# mixer.net
KiCad netlist of a schematic drawn in EAGLE
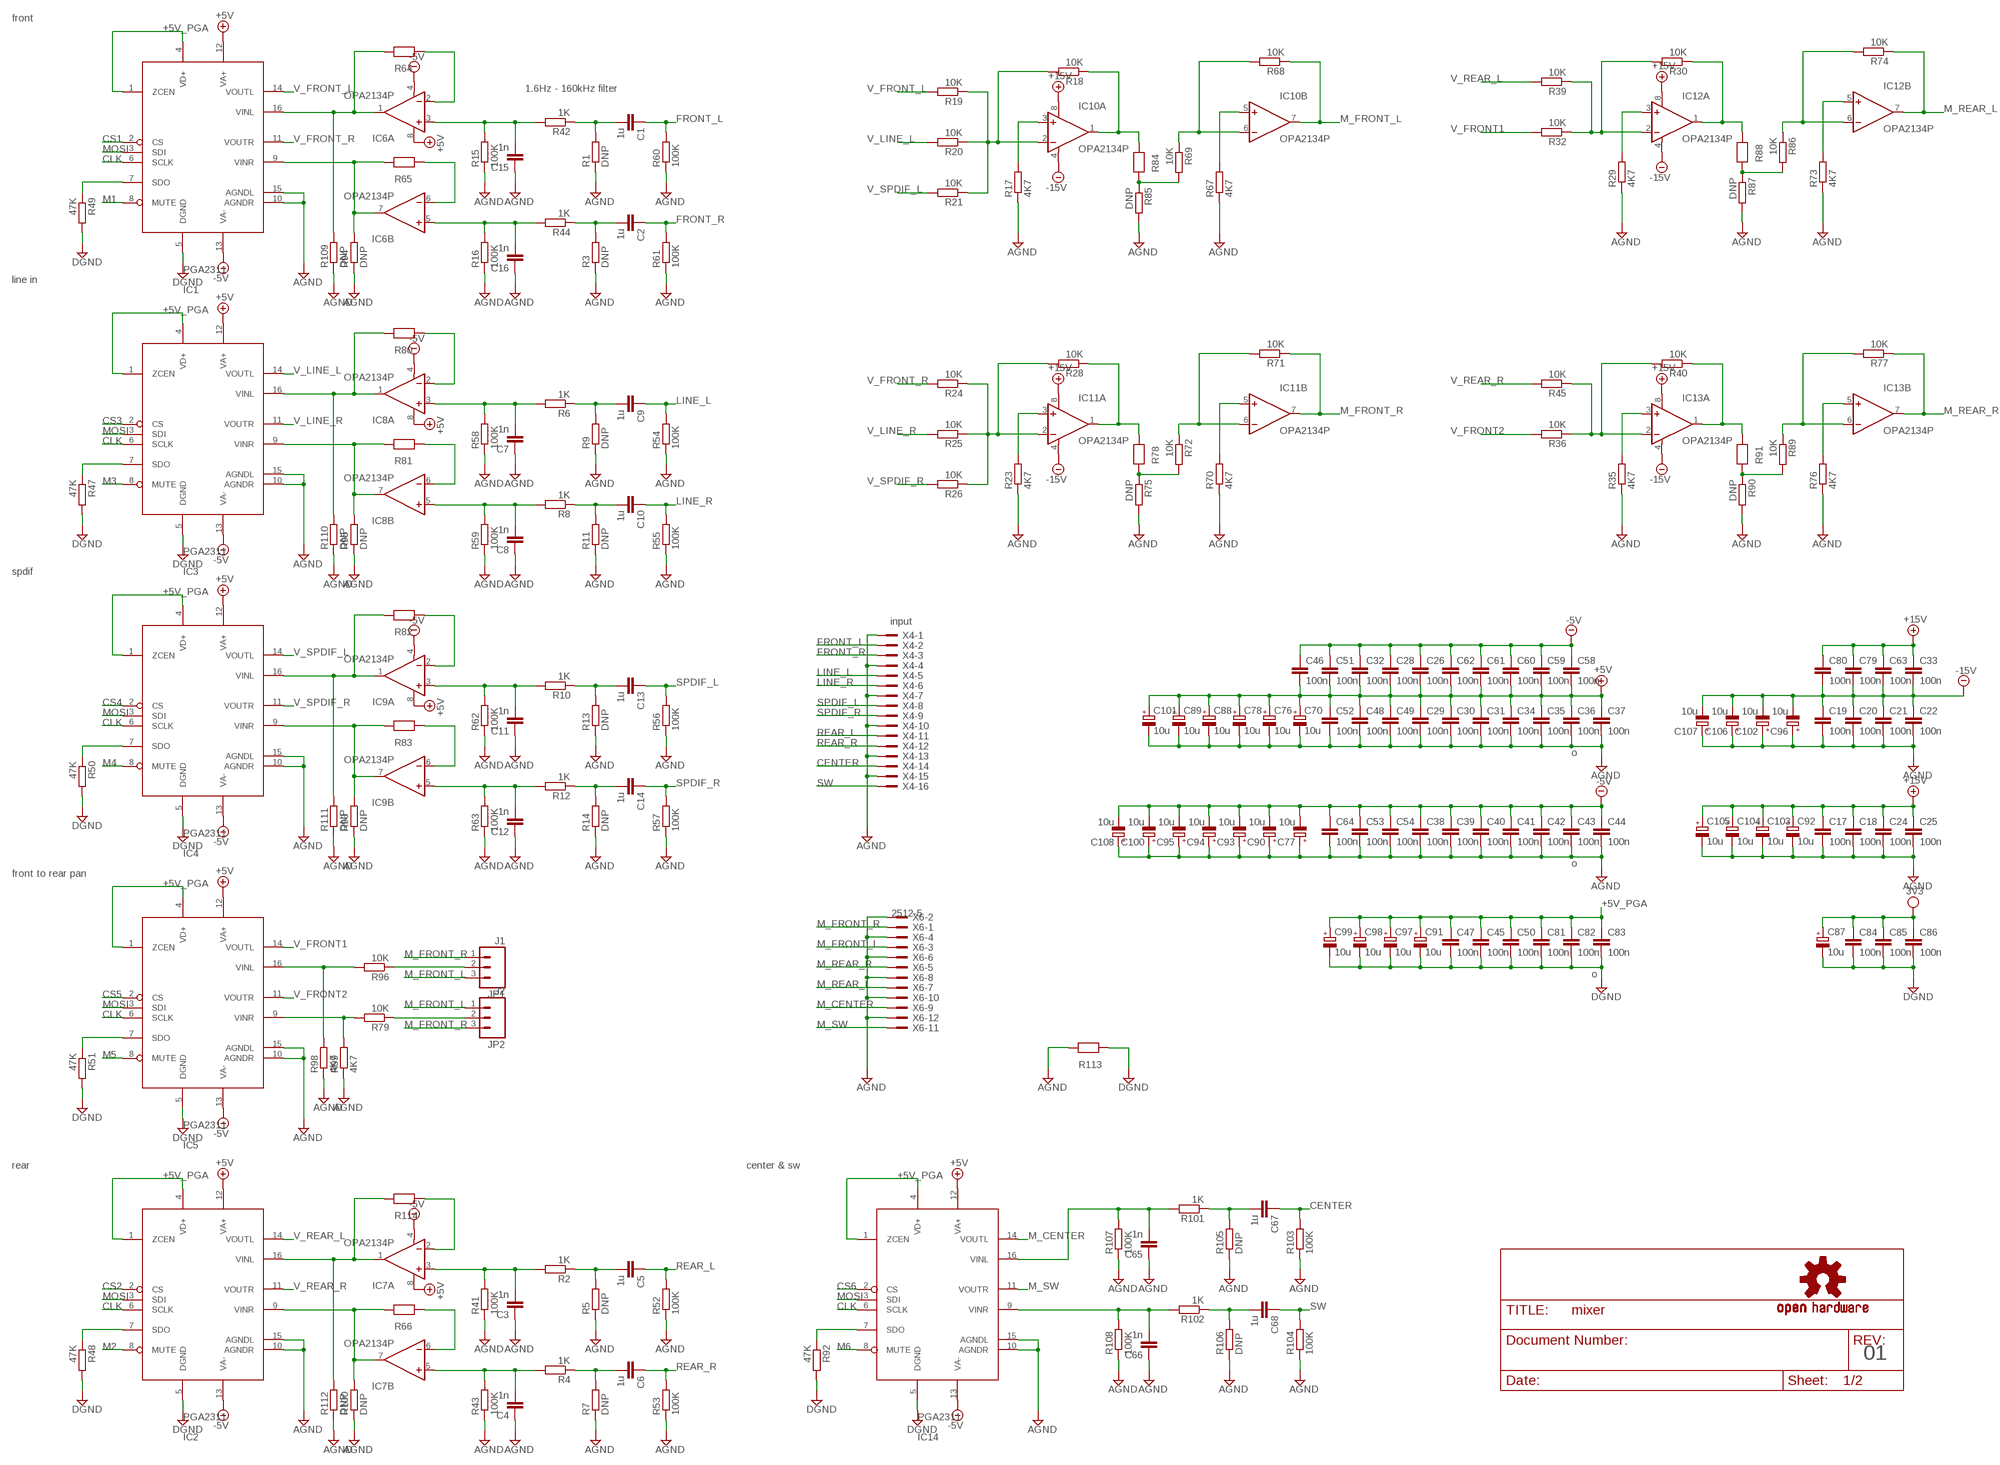
[diagram p0: schematic, sheet 1]
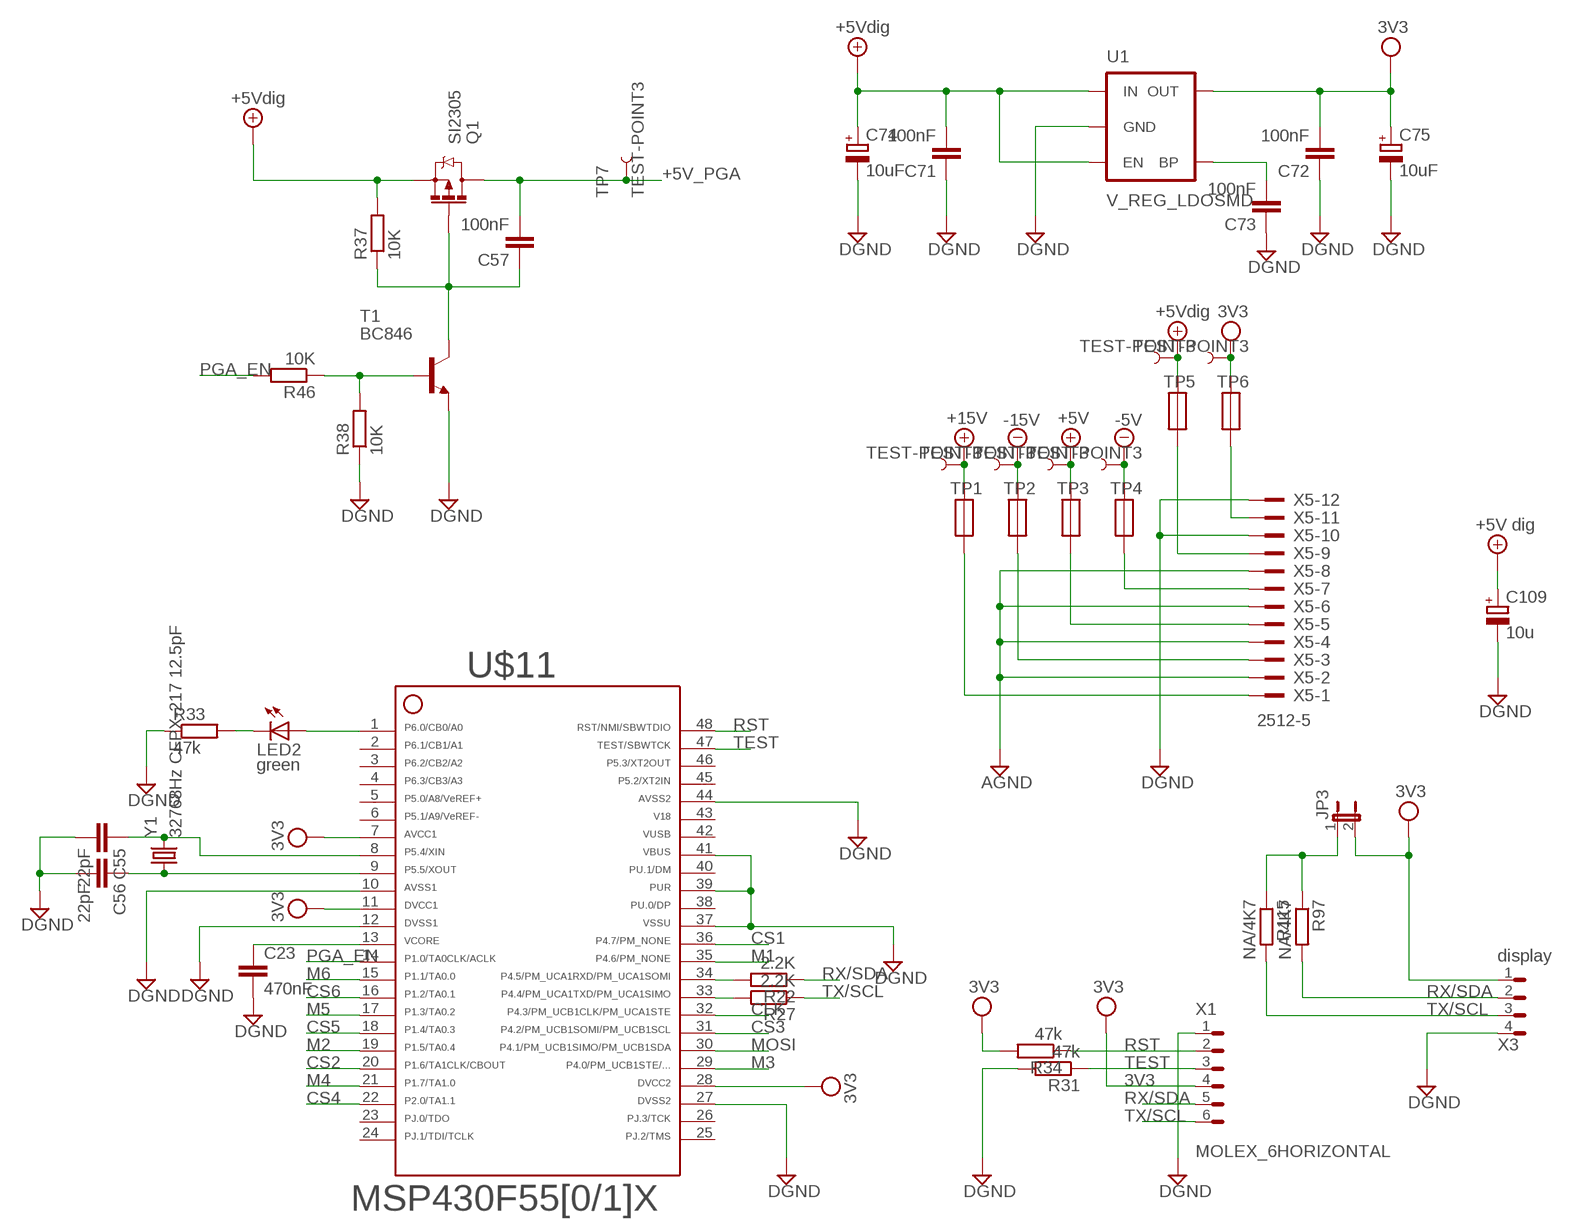
[diagram p1: schematic, sheet 2]

(export (version "E")
  (design (tool "Eeschema 10.0.6"))
  (components
    (comp (ref "C23")
      (value "470nF")
      (footprint "eagle-import:C0805")
      (libsource (lib "eagle-import") (part "C-EUC0805"))
    )
    (comp (ref "C55")
      (value "22pF")
      (footprint "eagle-import:C0805")
      (libsource (lib "eagle-import") (part "C-EUC0805"))
    )
    (comp (ref "C56")
      (value "22pF")
      (footprint "eagle-import:C0805")
      (libsource (lib "eagle-import") (part "C-EUC0805"))
    )
    (comp (ref "C57")
      (value "100nF")
      (footprint "eagle-import:C0805")
      (libsource (lib "eagle-import") (part "C-EUC0805"))
    )
    (comp (ref "C71")
      (value "100nF")
      (footprint "eagle-import:C0805")
      (libsource (lib "eagle-import") (part "C-EUC0805"))
    )
    (comp (ref "C72")
      (value "100nF")
      (footprint "eagle-import:C0805")
      (libsource (lib "eagle-import") (part "C-EUC0805"))
    )
    (comp (ref "C73")
      (value "100nF")
      (footprint "eagle-import:C0805")
      (libsource (lib "eagle-import") (part "C-EUC0805"))
    )
    (comp (ref "C74")
      (value "10uF")
      (footprint "eagle-import:153CLV-0405")
      (libsource (lib "eagle-import") (part "resistor_CPOL-EU153CLV-0405"))
    )
    (comp (ref "C75")
      (value "10uF")
      (footprint "eagle-import:153CLV-0405")
      (libsource (lib "eagle-import") (part "resistor_CPOL-EU153CLV-0405"))
    )
    (comp (ref "C109")
      (value "10u")
      (footprint "eagle-import:153CLV-0405")
      (libsource (lib "eagle-import") (part "CPOL-EU153CLV-0405"))
    )
    (comp (ref "JP3")
      (value "JUMPER-2SMD-NO")
      (footprint "eagle-import:SJ_2S-NO")
      (libsource (lib "eagle-import") (part "JUMPER-2SMD-NO"))
    )
    (comp (ref "LED2")
      (value "green")
      (footprint "eagle-import:CHIPLED_0805")
      (libsource (lib "eagle-import") (part "LEDCHIPLED_0805"))
    )
    (comp (ref "Q1")
      (value "SI2305")
      (footprint "eagle-import:SOT23-3_POWER")
      (libsource (lib "eagle-import") (part "MOSFET-PCHANNEL_SOT23-3_POWER"))
    )
    (comp (ref "R22")
      (value "2.2K")
      (footprint "eagle-import:R0805W")
      (libsource (lib "eagle-import") (part "R-EU_R0805W"))
    )
    (comp (ref "R27")
      (value "2.2K")
      (footprint "eagle-import:R0805W")
      (libsource (lib "eagle-import") (part "R-EU_R0805W"))
    )
    (comp (ref "R31")
      (value "47k")
      (footprint "eagle-import:R0805W")
      (libsource (lib "eagle-import") (part "R-EU_R0805W"))
    )
    (comp (ref "R33")
      (value "47k")
      (footprint "eagle-import:R0805W")
      (libsource (lib "eagle-import") (part "R-EU_R0805W"))
    )
    (comp (ref "R34")
      (value "47k")
      (footprint "eagle-import:R0805W")
      (libsource (lib "eagle-import") (part "R-EU_R0805W"))
    )
    (comp (ref "R37")
      (value "10K")
      (footprint "eagle-import:R0805W")
      (libsource (lib "eagle-import") (part "R-EU_R0805W"))
    )
    (comp (ref "R38")
      (value "10K")
      (footprint "eagle-import:R0805W")
      (libsource (lib "eagle-import") (part "R-EU_R0805W"))
    )
    (comp (ref "R46")
      (value "10K")
      (footprint "eagle-import:R0805W")
      (libsource (lib "eagle-import") (part "R-EU_R0805W"))
    )
    (comp (ref "R97")
      (value "NA/4K7")
      (footprint "eagle-import:R0805W")
      (libsource (lib "eagle-import") (part "R-EU_R0805W"))
    )
    (comp (ref "R115")
      (value "NA/4K7")
      (footprint "eagle-import:R0805W")
      (libsource (lib "eagle-import") (part "R-EU_R0805W"))
    )
    (comp (ref "T1")
      (value "BC846")
      (footprint "eagle-import:SOT23")
      (libsource (lib "eagle-import") (part "BC846"))
    )
    (comp (ref "TP1")
      (value "TEST-POINT3")
      (footprint "eagle-import:PAD.03X.03")
      (libsource (lib "eagle-import") (part "TEST-POINT3"))
    )
    (comp (ref "TP2")
      (value "TEST-POINT3")
      (footprint "eagle-import:PAD.03X.03")
      (libsource (lib "eagle-import") (part "TEST-POINT3"))
    )
    (comp (ref "TP3")
      (value "TEST-POINT3")
      (footprint "eagle-import:PAD.03X.03")
      (libsource (lib "eagle-import") (part "TEST-POINT3"))
    )
    (comp (ref "TP4")
      (value "TEST-POINT3")
      (footprint "eagle-import:PAD.03X.03")
      (libsource (lib "eagle-import") (part "TEST-POINT3"))
    )
    (comp (ref "TP5")
      (value "TEST-POINT3")
      (footprint "eagle-import:PAD.03X.03")
      (libsource (lib "eagle-import") (part "TEST-POINT3"))
    )
    (comp (ref "TP6")
      (value "TEST-POINT3")
      (footprint "eagle-import:PAD.03X.03")
      (libsource (lib "eagle-import") (part "TEST-POINT3"))
    )
    (comp (ref "TP7")
      (value "TEST-POINT3")
      (footprint "eagle-import:PAD.03X.03")
      (libsource (lib "eagle-import") (part "TEST-POINT3"))
    )
    (comp (ref "U$2")
      (value "RESETTABLE")
      (footprint "eagle-import:1210")
      (libsource (lib "eagle-import") (part "RESETTABLE"))
    )
    (comp (ref "U$5")
      (value "RESETTABLE")
      (footprint "eagle-import:1210")
      (libsource (lib "eagle-import") (part "RESETTABLE"))
    )
    (comp (ref "U$6")
      (value "RESETTABLE")
      (footprint "eagle-import:1210")
      (libsource (lib "eagle-import") (part "RESETTABLE"))
    )
    (comp (ref "U$9")
      (value "RESETTABLE")
      (footprint "eagle-import:1210")
      (libsource (lib "eagle-import") (part "RESETTABLE"))
    )
    (comp (ref "U$11")
      (value "F55[0/1]X---PT48")
      (footprint "eagle-import:PT48")
      (libsource (lib "eagle-import") (part "F55[0/1]X---PT48"))
    )
    (comp (ref "U$12")
      (value "RESETTABLE")
      (footprint "eagle-import:1210")
      (libsource (lib "eagle-import") (part "RESETTABLE"))
    )
    (comp (ref "U$13")
      (value "RESETTABLE")
      (footprint "eagle-import:1210")
      (libsource (lib "eagle-import") (part "RESETTABLE"))
    )
    (comp (ref "U1")
      (value "V_REG_LDOSMD")
      (footprint "eagle-import:SOT23-5")
      (libsource (lib "eagle-import") (part "V_REG_LDOSMD"))
    )
    (comp (ref "X1")
      (value "MOLEX_6HORIZONTAL")
      (footprint "eagle-import:0530480610")
      (libsource (lib "eagle-import") (part "MOLEX_6HORIZONTAL"))
    )
    (comp (ref "X3")
      (value "display")
      (footprint "eagle-import:0530480401")
      (libsource (lib "eagle-import") (part "MOLEX_4HORIZONTAL"))
    )
    (comp (ref "X5")
      (value "2512-5")
      (footprint "eagle-import:PAK100_2500-5-12")
      (fields (field (name "MPN") "N2514-5002RB"))
      (libsource (lib "eagle-import") (part "2512-5"))
    )
    (comp (ref "Y1")
      (value "32768Hz CFPX-217 12.5pF")
      (footprint "eagle-import:CRYSTAL-SMD-3.2X1.5")
      (libsource (lib "eagle-import") (part "CRYSTAL3.2X1.5"))
    )
    (comp (ref "C1")
      (value "1u")
      (footprint "eagle-import:C0805")
      (libsource (lib "eagle-import") (part "C-EUC0805"))
    )
    (comp (ref "C2")
      (value "1u")
      (footprint "eagle-import:C0805")
      (libsource (lib "eagle-import") (part "C-EUC0805"))
    )
    (comp (ref "C3")
      (value "1n")
      (footprint "eagle-import:C0805")
      (libsource (lib "eagle-import") (part "C-EUC0805"))
    )
    (comp (ref "C4")
      (value "1n")
      (footprint "eagle-import:C0805")
      (libsource (lib "eagle-import") (part "C-EUC0805"))
    )
    (comp (ref "C5")
      (value "1u")
      (footprint "eagle-import:C0805")
      (libsource (lib "eagle-import") (part "C-EUC0805"))
    )
    (comp (ref "C6")
      (value "1u")
      (footprint "eagle-import:C0805")
      (libsource (lib "eagle-import") (part "C-EUC0805"))
    )
    (comp (ref "C7")
      (value "1n")
      (footprint "eagle-import:C0805")
      (libsource (lib "eagle-import") (part "C-EUC0805"))
    )
    (comp (ref "C8")
      (value "1n")
      (footprint "eagle-import:C0805")
      (libsource (lib "eagle-import") (part "C-EUC0805"))
    )
    (comp (ref "C9")
      (value "1u")
      (footprint "eagle-import:C0805")
      (libsource (lib "eagle-import") (part "C-EUC0805"))
    )
    (comp (ref "C10")
      (value "1u")
      (footprint "eagle-import:C0805")
      (libsource (lib "eagle-import") (part "C-EUC0805"))
    )
    (comp (ref "C11")
      (value "1n")
      (footprint "eagle-import:C0805")
      (libsource (lib "eagle-import") (part "C-EUC0805"))
    )
    (comp (ref "C12")
      (value "1n")
      (footprint "eagle-import:C0805")
      (libsource (lib "eagle-import") (part "C-EUC0805"))
    )
    (comp (ref "C13")
      (value "1u")
      (footprint "eagle-import:C0805")
      (libsource (lib "eagle-import") (part "C-EUC0805"))
    )
    (comp (ref "C14")
      (value "1u")
      (footprint "eagle-import:C0805")
      (libsource (lib "eagle-import") (part "C-EUC0805"))
    )
    (comp (ref "C15")
      (value "1n")
      (footprint "eagle-import:C0805")
      (libsource (lib "eagle-import") (part "C-EUC0805"))
    )
    (comp (ref "C16")
      (value "1n")
      (footprint "eagle-import:C0805")
      (libsource (lib "eagle-import") (part "C-EUC0805"))
    )
    (comp (ref "C17")
      (value "100n")
      (footprint "eagle-import:C0805")
      (libsource (lib "eagle-import") (part "C-EUC0805"))
    )
    (comp (ref "C18")
      (value "100n")
      (footprint "eagle-import:C0805")
      (libsource (lib "eagle-import") (part "C-EUC0805"))
    )
    (comp (ref "C19")
      (value "100n")
      (footprint "eagle-import:C0805")
      (libsource (lib "eagle-import") (part "C-EUC0805"))
    )
    (comp (ref "C20")
      (value "100n")
      (footprint "eagle-import:C0805")
      (libsource (lib "eagle-import") (part "C-EUC0805"))
    )
    (comp (ref "C21")
      (value "100n")
      (footprint "eagle-import:C0805")
      (libsource (lib "eagle-import") (part "C-EUC0805"))
    )
    (comp (ref "C22")
      (value "100n")
      (footprint "eagle-import:C0805")
      (libsource (lib "eagle-import") (part "C-EUC0805"))
    )
    (comp (ref "C24")
      (value "100n")
      (footprint "eagle-import:C0805")
      (libsource (lib "eagle-import") (part "C-EUC0805"))
    )
    (comp (ref "C25")
      (value "100n")
      (footprint "eagle-import:C0805")
      (libsource (lib "eagle-import") (part "C-EUC0805"))
    )
    (comp (ref "C26")
      (value "100n")
      (footprint "eagle-import:C0805")
      (libsource (lib "eagle-import") (part "C-EUC0805"))
    )
    (comp (ref "C28")
      (value "100n")
      (footprint "eagle-import:C0805")
      (libsource (lib "eagle-import") (part "C-EUC0805"))
    )
    (comp (ref "C29")
      (value "100n")
      (footprint "eagle-import:C0805")
      (libsource (lib "eagle-import") (part "C-EUC0805"))
    )
    (comp (ref "C30")
      (value "100n")
      (footprint "eagle-import:C0805")
      (libsource (lib "eagle-import") (part "C-EUC0805"))
    )
    (comp (ref "C31")
      (value "100n")
      (footprint "eagle-import:C0805")
      (libsource (lib "eagle-import") (part "C-EUC0805"))
    )
    (comp (ref "C32")
      (value "100n")
      (footprint "eagle-import:C0805")
      (libsource (lib "eagle-import") (part "C-EUC0805"))
    )
    (comp (ref "C33")
      (value "100n")
      (footprint "eagle-import:C0805")
      (libsource (lib "eagle-import") (part "C-EUC0805"))
    )
    (comp (ref "C34")
      (value "100n")
      (footprint "eagle-import:C0805")
      (libsource (lib "eagle-import") (part "C-EUC0805"))
    )
    (comp (ref "C35")
      (value "100n")
      (footprint "eagle-import:C0805")
      (libsource (lib "eagle-import") (part "C-EUC0805"))
    )
    (comp (ref "C36")
      (value "100n")
      (footprint "eagle-import:C0805")
      (libsource (lib "eagle-import") (part "C-EUC0805"))
    )
    (comp (ref "C37")
      (value "100n")
      (footprint "eagle-import:C0805")
      (libsource (lib "eagle-import") (part "C-EUC0805"))
    )
    (comp (ref "C38")
      (value "100n")
      (footprint "eagle-import:C0805")
      (libsource (lib "eagle-import") (part "C-EUC0805"))
    )
    (comp (ref "C39")
      (value "100n")
      (footprint "eagle-import:C0805")
      (libsource (lib "eagle-import") (part "C-EUC0805"))
    )
    (comp (ref "C40")
      (value "100n")
      (footprint "eagle-import:C0805")
      (libsource (lib "eagle-import") (part "C-EUC0805"))
    )
    (comp (ref "C41")
      (value "100n")
      (footprint "eagle-import:C0805")
      (libsource (lib "eagle-import") (part "C-EUC0805"))
    )
    (comp (ref "C42")
      (value "100n")
      (footprint "eagle-import:C0805")
      (libsource (lib "eagle-import") (part "C-EUC0805"))
    )
    (comp (ref "C43")
      (value "100n")
      (footprint "eagle-import:C0805")
      (libsource (lib "eagle-import") (part "C-EUC0805"))
    )
    (comp (ref "C44")
      (value "100n")
      (footprint "eagle-import:C0805")
      (libsource (lib "eagle-import") (part "C-EUC0805"))
    )
    (comp (ref "C45")
      (value "100n")
      (footprint "eagle-import:C0805")
      (libsource (lib "eagle-import") (part "C-EUC0805"))
    )
    (comp (ref "C46")
      (value "100n")
      (footprint "eagle-import:C0805")
      (libsource (lib "eagle-import") (part "C-EUC0805"))
    )
    (comp (ref "C47")
      (value "100n")
      (footprint "eagle-import:C0805")
      (libsource (lib "eagle-import") (part "C-EUC0805"))
    )
    (comp (ref "C48")
      (value "100n")
      (footprint "eagle-import:C0805")
      (libsource (lib "eagle-import") (part "C-EUC0805"))
    )
    (comp (ref "C49")
      (value "100n")
      (footprint "eagle-import:C0805")
      (libsource (lib "eagle-import") (part "C-EUC0805"))
    )
    (comp (ref "C50")
      (value "100n")
      (footprint "eagle-import:C0805")
      (libsource (lib "eagle-import") (part "C-EUC0805"))
    )
    (comp (ref "C51")
      (value "100n")
      (footprint "eagle-import:C0805")
      (libsource (lib "eagle-import") (part "C-EUC0805"))
    )
    (comp (ref "C52")
      (value "100n")
      (footprint "eagle-import:C0805")
      (libsource (lib "eagle-import") (part "C-EUC0805"))
    )
    (comp (ref "C53")
      (value "100n")
      (footprint "eagle-import:C0805")
      (libsource (lib "eagle-import") (part "C-EUC0805"))
    )
    (comp (ref "C54")
      (value "100n")
      (footprint "eagle-import:C0805")
      (libsource (lib "eagle-import") (part "C-EUC0805"))
    )
    (comp (ref "C58")
      (value "100n")
      (footprint "eagle-import:C0805")
      (libsource (lib "eagle-import") (part "C-EUC0805"))
    )
    (comp (ref "C59")
      (value "100n")
      (footprint "eagle-import:C0805")
      (libsource (lib "eagle-import") (part "C-EUC0805"))
    )
    (comp (ref "C60")
      (value "100n")
      (footprint "eagle-import:C0805")
      (libsource (lib "eagle-import") (part "C-EUC0805"))
    )
    (comp (ref "C61")
      (value "100n")
      (footprint "eagle-import:C0805")
      (libsource (lib "eagle-import") (part "C-EUC0805"))
    )
    (comp (ref "C62")
      (value "100n")
      (footprint "eagle-import:C0805")
      (libsource (lib "eagle-import") (part "C-EUC0805"))
    )
    (comp (ref "C63")
      (value "100n")
      (footprint "eagle-import:C0805")
      (libsource (lib "eagle-import") (part "C-EUC0805"))
    )
    (comp (ref "C64")
      (value "100n")
      (footprint "eagle-import:C0805")
      (libsource (lib "eagle-import") (part "C-EUC0805"))
    )
    (comp (ref "C65")
      (value "1n")
      (footprint "eagle-import:C0805")
      (libsource (lib "eagle-import") (part "C-EUC0805"))
    )
    (comp (ref "C66")
      (value "1n")
      (footprint "eagle-import:C0805")
      (libsource (lib "eagle-import") (part "C-EUC0805"))
    )
    (comp (ref "C67")
      (value "1u")
      (footprint "eagle-import:C0805")
      (libsource (lib "eagle-import") (part "C-EUC0805"))
    )
    (comp (ref "C68")
      (value "1u")
      (footprint "eagle-import:C0805")
      (libsource (lib "eagle-import") (part "C-EUC0805"))
    )
    (comp (ref "C70")
      (value "10u")
      (footprint "eagle-import:153CLV-0405")
      (libsource (lib "eagle-import") (part "CPOL-EU153CLV-0405"))
    )
    (comp (ref "C76")
      (value "10u")
      (footprint "eagle-import:153CLV-0405")
      (libsource (lib "eagle-import") (part "CPOL-EU153CLV-0405"))
    )
    (comp (ref "C77")
      (value "10u")
      (footprint "eagle-import:153CLV-0405")
      (libsource (lib "eagle-import") (part "CPOL-EU153CLV-0405"))
    )
    (comp (ref "C78")
      (value "10u")
      (footprint "eagle-import:153CLV-0405")
      (libsource (lib "eagle-import") (part "CPOL-EU153CLV-0405"))
    )
    (comp (ref "C79")
      (value "100n")
      (footprint "eagle-import:C0805")
      (libsource (lib "eagle-import") (part "C-EUC0805"))
    )
    (comp (ref "C80")
      (value "100n")
      (footprint "eagle-import:C0805")
      (libsource (lib "eagle-import") (part "C-EUC0805"))
    )
    (comp (ref "C81")
      (value "100n")
      (footprint "eagle-import:C0805")
      (libsource (lib "eagle-import") (part "C-EUC0805"))
    )
    (comp (ref "C82")
      (value "100n")
      (footprint "eagle-import:C0805")
      (libsource (lib "eagle-import") (part "C-EUC0805"))
    )
    (comp (ref "C83")
      (value "100n")
      (footprint "eagle-import:C0805")
      (libsource (lib "eagle-import") (part "C-EUC0805"))
    )
    (comp (ref "C84")
      (value "100n")
      (footprint "eagle-import:C0805")
      (libsource (lib "eagle-import") (part "C-EUC0805"))
    )
    (comp (ref "C85")
      (value "100n")
      (footprint "eagle-import:C0805")
      (libsource (lib "eagle-import") (part "C-EUC0805"))
    )
    (comp (ref "C86")
      (value "100n")
      (footprint "eagle-import:C0805")
      (libsource (lib "eagle-import") (part "C-EUC0805"))
    )
    (comp (ref "C87")
      (value "10u")
      (footprint "eagle-import:153CLV-0405")
      (libsource (lib "eagle-import") (part "CPOL-EU153CLV-0405"))
    )
    (comp (ref "C88")
      (value "10u")
      (footprint "eagle-import:153CLV-0405")
      (libsource (lib "eagle-import") (part "CPOL-EU153CLV-0405"))
    )
    (comp (ref "C89")
      (value "10u")
      (footprint "eagle-import:153CLV-0405")
      (libsource (lib "eagle-import") (part "CPOL-EU153CLV-0405"))
    )
    (comp (ref "C90")
      (value "10u")
      (footprint "eagle-import:153CLV-0405")
      (libsource (lib "eagle-import") (part "CPOL-EU153CLV-0405"))
    )
    (comp (ref "C91")
      (value "10u")
      (footprint "eagle-import:153CLV-0405")
      (libsource (lib "eagle-import") (part "CPOL-EU153CLV-0405"))
    )
    (comp (ref "C92")
      (value "10u")
      (footprint "eagle-import:153CLV-0405")
      (libsource (lib "eagle-import") (part "CPOL-EU153CLV-0405"))
    )
    (comp (ref "C93")
      (value "10u")
      (footprint "eagle-import:153CLV-0405")
      (libsource (lib "eagle-import") (part "CPOL-EU153CLV-0405"))
    )
    (comp (ref "C94")
      (value "10u")
      (footprint "eagle-import:153CLV-0405")
      (libsource (lib "eagle-import") (part "CPOL-EU153CLV-0405"))
    )
    (comp (ref "C95")
      (value "10u")
      (footprint "eagle-import:153CLV-0405")
      (libsource (lib "eagle-import") (part "CPOL-EU153CLV-0405"))
    )
    (comp (ref "C96")
      (value "10u")
      (footprint "eagle-import:153CLV-0405")
      (libsource (lib "eagle-import") (part "CPOL-EU153CLV-0405"))
    )
    (comp (ref "C97")
      (value "10u")
      (footprint "eagle-import:153CLV-0405")
      (libsource (lib "eagle-import") (part "CPOL-EU153CLV-0405"))
    )
    (comp (ref "C98")
      (value "10u")
      (footprint "eagle-import:153CLV-0405")
      (libsource (lib "eagle-import") (part "CPOL-EU153CLV-0405"))
    )
    (comp (ref "C99")
      (value "10u")
      (footprint "eagle-import:153CLV-0405")
      (libsource (lib "eagle-import") (part "CPOL-EU153CLV-0405"))
    )
    (comp (ref "C100")
      (value "10u")
      (footprint "eagle-import:153CLV-0405")
      (libsource (lib "eagle-import") (part "CPOL-EU153CLV-0405"))
    )
    (comp (ref "C101")
      (value "10u")
      (footprint "eagle-import:153CLV-0405")
      (libsource (lib "eagle-import") (part "CPOL-EU153CLV-0405"))
    )
    (comp (ref "C102")
      (value "10u")
      (footprint "eagle-import:153CLV-0405")
      (libsource (lib "eagle-import") (part "CPOL-EU153CLV-0405"))
    )
    (comp (ref "C103")
      (value "10u")
      (footprint "eagle-import:153CLV-0405")
      (libsource (lib "eagle-import") (part "CPOL-EU153CLV-0405"))
    )
    (comp (ref "C104")
      (value "10u")
      (footprint "eagle-import:153CLV-0405")
      (libsource (lib "eagle-import") (part "CPOL-EU153CLV-0405"))
    )
    (comp (ref "C105")
      (value "10u")
      (footprint "eagle-import:153CLV-0405")
      (libsource (lib "eagle-import") (part "CPOL-EU153CLV-0405"))
    )
    (comp (ref "C106")
      (value "10u")
      (footprint "eagle-import:153CLV-0405")
      (libsource (lib "eagle-import") (part "CPOL-EU153CLV-0405"))
    )
    (comp (ref "C107")
      (value "10u")
      (footprint "eagle-import:153CLV-0405")
      (libsource (lib "eagle-import") (part "CPOL-EU153CLV-0405"))
    )
    (comp (ref "C108")
      (value "10u")
      (footprint "eagle-import:153CLV-0405")
      (libsource (lib "eagle-import") (part "CPOL-EU153CLV-0405"))
    )
    (comp (ref "IC1")
      (value "PGA2311")
      (footprint "eagle-import:SO-16")
      (libsource (lib "eagle-import") (part "PGA2311"))
    )
    (comp (ref "IC2")
      (value "PGA2311")
      (footprint "eagle-import:SO-16")
      (libsource (lib "eagle-import") (part "PGA2311"))
    )
    (comp (ref "IC3")
      (value "PGA2311")
      (footprint "eagle-import:SO-16")
      (libsource (lib "eagle-import") (part "PGA2311"))
    )
    (comp (ref "IC4")
      (value "PGA2311")
      (footprint "eagle-import:SO-16")
      (libsource (lib "eagle-import") (part "PGA2311"))
    )
    (comp (ref "IC5")
      (value "PGA2311")
      (footprint "eagle-import:SO-16")
      (libsource (lib "eagle-import") (part "PGA2311"))
    )
    (comp (ref "IC6")
      (value "OPA2134P")
      (footprint "eagle-import:DIL08")
      (fields (field (name "MF") "TEXAS INSTRUMENTS") (field (name "MPN") "OPA2134PA"))
      (libsource (lib "eagle-import") (part "OPA2134P"))
    )
    (comp (ref "IC7")
      (value "OPA2134P")
      (footprint "eagle-import:DIL08")
      (fields (field (name "MF") "TEXAS INSTRUMENTS") (field (name "MPN") "OPA2134PA"))
      (libsource (lib "eagle-import") (part "OPA2134P"))
    )
    (comp (ref "IC8")
      (value "OPA2134P")
      (footprint "eagle-import:DIL08")
      (fields (field (name "MF") "TEXAS INSTRUMENTS") (field (name "MPN") "OPA2134PA"))
      (libsource (lib "eagle-import") (part "OPA2134P"))
    )
    (comp (ref "IC9")
      (value "OPA2134P")
      (footprint "eagle-import:DIL08")
      (fields (field (name "MF") "TEXAS INSTRUMENTS") (field (name "MPN") "OPA2134PA"))
      (libsource (lib "eagle-import") (part "OPA2134P"))
    )
    (comp (ref "IC10")
      (value "OPA2134P")
      (footprint "eagle-import:DIL08")
      (fields (field (name "MF") "TEXAS INSTRUMENTS") (field (name "MPN") "OPA2134PA"))
      (libsource (lib "eagle-import") (part "OPA2134P"))
    )
    (comp (ref "IC11")
      (value "OPA2134P")
      (footprint "eagle-import:DIL08")
      (fields (field (name "MF") "TEXAS INSTRUMENTS") (field (name "MPN") "OPA2134PA"))
      (libsource (lib "eagle-import") (part "OPA2134P"))
    )
    (comp (ref "IC12")
      (value "OPA2134P")
      (footprint "eagle-import:DIL08")
      (fields (field (name "MF") "TEXAS INSTRUMENTS") (field (name "MPN") "OPA2134PA"))
      (libsource (lib "eagle-import") (part "OPA2134P"))
    )
    (comp (ref "IC13")
      (value "OPA2134P")
      (footprint "eagle-import:DIL08")
      (fields (field (name "MF") "TEXAS INSTRUMENTS") (field (name "MPN") "OPA2134PA"))
      (libsource (lib "eagle-import") (part "OPA2134P"))
    )
    (comp (ref "IC14")
      (value "PGA2311")
      (footprint "eagle-import:SO-16")
      (libsource (lib "eagle-import") (part "PGA2311"))
    )
    (comp (ref "JP1")
      (value "J1")
      (footprint "eagle-import:1X03")
      (libsource (lib "eagle-import") (part "M03PTH"))
    )
    (comp (ref "JP2")
      (value "J2")
      (footprint "eagle-import:1X03")
      (libsource (lib "eagle-import") (part "M03PTH"))
    )
    (comp (ref "R1")
      (value "DNP")
      (footprint "eagle-import:R0805W")
      (libsource (lib "eagle-import") (part "R-EU_R0805W"))
    )
    (comp (ref "R2")
      (value "1K")
      (footprint "eagle-import:R0805W")
      (libsource (lib "eagle-import") (part "R-EU_R0805W"))
    )
    (comp (ref "R3")
      (value "DNP")
      (footprint "eagle-import:R0805W")
      (libsource (lib "eagle-import") (part "R-EU_R0805W"))
    )
    (comp (ref "R4")
      (value "1K")
      (footprint "eagle-import:R0805W")
      (libsource (lib "eagle-import") (part "R-EU_R0805W"))
    )
    (comp (ref "R5")
      (value "DNP")
      (footprint "eagle-import:R0805W")
      (libsource (lib "eagle-import") (part "R-EU_R0805W"))
    )
    (comp (ref "R6")
      (value "1K")
      (footprint "eagle-import:R0805W")
      (libsource (lib "eagle-import") (part "R-EU_R0805W"))
    )
    (comp (ref "R7")
      (value "DNP")
      (footprint "eagle-import:R0805W")
      (libsource (lib "eagle-import") (part "R-EU_R0805W"))
    )
    (comp (ref "R8")
      (value "1K")
      (footprint "eagle-import:R0805W")
      (libsource (lib "eagle-import") (part "R-EU_R0805W"))
    )
    (comp (ref "R9")
      (value "DNP")
      (footprint "eagle-import:R0805W")
      (libsource (lib "eagle-import") (part "R-EU_R0805W"))
    )
    (comp (ref "R10")
      (value "1K")
      (footprint "eagle-import:R0805W")
      (libsource (lib "eagle-import") (part "R-EU_R0805W"))
    )
    (comp (ref "R11")
      (value "DNP")
      (footprint "eagle-import:R0805W")
      (libsource (lib "eagle-import") (part "R-EU_R0805W"))
    )
    (comp (ref "R12")
      (value "1K")
      (footprint "eagle-import:R0805W")
      (libsource (lib "eagle-import") (part "R-EU_R0805W"))
    )
    (comp (ref "R13")
      (value "DNP")
      (footprint "eagle-import:R0805W")
      (libsource (lib "eagle-import") (part "R-EU_R0805W"))
    )
    (comp (ref "R14")
      (value "DNP")
      (footprint "eagle-import:R0805W")
      (libsource (lib "eagle-import") (part "R-EU_R0805W"))
    )
    (comp (ref "R15")
      (value "100K")
      (footprint "eagle-import:R0805W")
      (libsource (lib "eagle-import") (part "R-EU_R0805W"))
    )
    (comp (ref "R16")
      (value "100K")
      (footprint "eagle-import:R0805W")
      (libsource (lib "eagle-import") (part "R-EU_R0805W"))
    )
    (comp (ref "R17")
      (value "4K7")
      (footprint "eagle-import:R0805W")
      (libsource (lib "eagle-import") (part "R-EU_R0805W"))
    )
    (comp (ref "R18")
      (value "10K")
      (footprint "eagle-import:R0805W")
      (libsource (lib "eagle-import") (part "R-EU_R0805W"))
    )
    (comp (ref "R19")
      (value "10K")
      (footprint "eagle-import:R0805W")
      (libsource (lib "eagle-import") (part "R-EU_R0805W"))
    )
    (comp (ref "R20")
      (value "10K")
      (footprint "eagle-import:R0805W")
      (libsource (lib "eagle-import") (part "R-EU_R0805W"))
    )
    (comp (ref "R21")
      (value "10K")
      (footprint "eagle-import:R0805W")
      (libsource (lib "eagle-import") (part "R-EU_R0805W"))
    )
    (comp (ref "R23")
      (value "4K7")
      (footprint "eagle-import:R0805W")
      (libsource (lib "eagle-import") (part "R-EU_R0805W"))
    )
    (comp (ref "R24")
      (value "10K")
      (footprint "eagle-import:R0805W")
      (libsource (lib "eagle-import") (part "R-EU_R0805W"))
    )
    (comp (ref "R25")
      (value "10K")
      (footprint "eagle-import:R0805W")
      (libsource (lib "eagle-import") (part "R-EU_R0805W"))
    )
    (comp (ref "R26")
      (value "10K")
      (footprint "eagle-import:R0805W")
      (libsource (lib "eagle-import") (part "R-EU_R0805W"))
    )
    (comp (ref "R28")
      (value "10K")
      (footprint "eagle-import:R0805W")
      (libsource (lib "eagle-import") (part "R-EU_R0805W"))
    )
    (comp (ref "R29")
      (value "4K7")
      (footprint "eagle-import:R0805W")
      (libsource (lib "eagle-import") (part "R-EU_R0805W"))
    )
    (comp (ref "R30")
      (value "10K")
      (footprint "eagle-import:R0805W")
      (libsource (lib "eagle-import") (part "R-EU_R0805W"))
    )
    (comp (ref "R32")
      (value "10K")
      (footprint "eagle-import:R0805W")
      (libsource (lib "eagle-import") (part "R-EU_R0805W"))
    )
    (comp (ref "R35")
      (value "4K7")
      (footprint "eagle-import:R0805W")
      (libsource (lib "eagle-import") (part "R-EU_R0805W"))
    )
    (comp (ref "R36")
      (value "10K")
      (footprint "eagle-import:R0805W")
      (libsource (lib "eagle-import") (part "R-EU_R0805W"))
    )
    (comp (ref "R39")
      (value "10K")
      (footprint "eagle-import:R0805W")
      (libsource (lib "eagle-import") (part "R-EU_R0805W"))
    )
    (comp (ref "R40")
      (value "10K")
      (footprint "eagle-import:R0805W")
      (libsource (lib "eagle-import") (part "R-EU_R0805W"))
    )
    (comp (ref "R41")
      (value "100K")
      (footprint "eagle-import:R0805W")
      (libsource (lib "eagle-import") (part "R-EU_R0805W"))
    )
    (comp (ref "R42")
      (value "1K")
      (footprint "eagle-import:R0805W")
      (libsource (lib "eagle-import") (part "R-EU_R0805W"))
    )
    (comp (ref "R43")
      (value "100K")
      (footprint "eagle-import:R0805W")
      (libsource (lib "eagle-import") (part "R-EU_R0805W"))
    )
    (comp (ref "R44")
      (value "1K")
      (footprint "eagle-import:R0805W")
      (libsource (lib "eagle-import") (part "R-EU_R0805W"))
    )
    (comp (ref "R45")
      (value "10K")
      (footprint "eagle-import:R0805W")
      (libsource (lib "eagle-import") (part "R-EU_R0805W"))
    )
    (comp (ref "R47")
      (value "47K")
      (footprint "eagle-import:R0805W")
      (libsource (lib "eagle-import") (part "R-EU_R0805W"))
    )
    (comp (ref "R48")
      (value "47K")
      (footprint "eagle-import:R0805W")
      (libsource (lib "eagle-import") (part "R-EU_R0805W"))
    )
    (comp (ref "R49")
      (value "47K")
      (footprint "eagle-import:R0805W")
      (libsource (lib "eagle-import") (part "R-EU_R0805W"))
    )
    (comp (ref "R50")
      (value "47K")
      (footprint "eagle-import:R0805W")
      (libsource (lib "eagle-import") (part "R-EU_R0805W"))
    )
    (comp (ref "R51")
      (value "47K")
      (footprint "eagle-import:R0805W")
      (libsource (lib "eagle-import") (part "R-EU_R0805W"))
    )
    (comp (ref "R52")
      (value "100K")
      (footprint "eagle-import:R0805W")
      (libsource (lib "eagle-import") (part "R-EU_R0805W"))
    )
    (comp (ref "R53")
      (value "100K")
      (footprint "eagle-import:R0805W")
      (libsource (lib "eagle-import") (part "R-EU_R0805W"))
    )
    (comp (ref "R54")
      (value "100K")
      (footprint "eagle-import:R0805W")
      (libsource (lib "eagle-import") (part "R-EU_R0805W"))
    )
    (comp (ref "R55")
      (value "100K")
      (footprint "eagle-import:R0805W")
      (libsource (lib "eagle-import") (part "R-EU_R0805W"))
    )
    (comp (ref "R56")
      (value "100K")
      (footprint "eagle-import:R0805W")
      (libsource (lib "eagle-import") (part "R-EU_R0805W"))
    )
    (comp (ref "R57")
      (value "100K")
      (footprint "eagle-import:R0805W")
      (libsource (lib "eagle-import") (part "R-EU_R0805W"))
    )
    (comp (ref "R58")
      (value "100K")
      (footprint "eagle-import:R0805W")
      (libsource (lib "eagle-import") (part "R-EU_R0805W"))
    )
    (comp (ref "R59")
      (value "100K")
      (footprint "eagle-import:R0805W")
      (libsource (lib "eagle-import") (part "R-EU_R0805W"))
    )
    (comp (ref "R60")
      (value "100K")
      (footprint "eagle-import:R0805W")
      (libsource (lib "eagle-import") (part "R-EU_R0805W"))
    )
    (comp (ref "R61")
      (value "100K")
      (footprint "eagle-import:R0805W")
      (libsource (lib "eagle-import") (part "R-EU_R0805W"))
    )
    (comp (ref "R62")
      (value "100K")
      (footprint "eagle-import:R0805W")
      (libsource (lib "eagle-import") (part "R-EU_R0805W"))
    )
    (comp (ref "R63")
      (value "100K")
      (footprint "eagle-import:R0805W")
      (libsource (lib "eagle-import") (part "R-EU_R0805W"))
    )
    (comp (ref "R64")
      (value "0R_0805")
      (footprint "eagle-import:R0805W")
      (libsource (lib "eagle-import") (part "0R_0805"))
    )
    (comp (ref "R65")
      (value "0R_0805")
      (footprint "eagle-import:R0805W")
      (libsource (lib "eagle-import") (part "0R_0805"))
    )
    (comp (ref "R66")
      (value "0R_0805")
      (footprint "eagle-import:R0805W")
      (libsource (lib "eagle-import") (part "0R_0805"))
    )
    (comp (ref "R67")
      (value "4K7")
      (footprint "eagle-import:R0805W")
      (libsource (lib "eagle-import") (part "R-EU_R0805W"))
    )
    (comp (ref "R68")
      (value "10K")
      (footprint "eagle-import:R0805W")
      (libsource (lib "eagle-import") (part "R-EU_R0805W"))
    )
    (comp (ref "R69")
      (value "10K")
      (footprint "eagle-import:R0805W")
      (libsource (lib "eagle-import") (part "R-EU_R0805W"))
    )
    (comp (ref "R70")
      (value "4K7")
      (footprint "eagle-import:R0805W")
      (libsource (lib "eagle-import") (part "R-EU_R0805W"))
    )
    (comp (ref "R71")
      (value "10K")
      (footprint "eagle-import:R0805W")
      (libsource (lib "eagle-import") (part "R-EU_R0805W"))
    )
    (comp (ref "R72")
      (value "10K")
      (footprint "eagle-import:R0805W")
      (libsource (lib "eagle-import") (part "R-EU_R0805W"))
    )
    (comp (ref "R73")
      (value "4K7")
      (footprint "eagle-import:R0805W")
      (libsource (lib "eagle-import") (part "R-EU_R0805W"))
    )
    (comp (ref "R74")
      (value "10K")
      (footprint "eagle-import:R0805W")
      (libsource (lib "eagle-import") (part "R-EU_R0805W"))
    )
    (comp (ref "R75")
      (value "DNP")
      (footprint "eagle-import:R0805W")
      (libsource (lib "eagle-import") (part "R-EU_R0805W"))
    )
    (comp (ref "R76")
      (value "4K7")
      (footprint "eagle-import:R0805W")
      (libsource (lib "eagle-import") (part "R-EU_R0805W"))
    )
    (comp (ref "R77")
      (value "10K")
      (footprint "eagle-import:R0805W")
      (libsource (lib "eagle-import") (part "R-EU_R0805W"))
    )
    (comp (ref "R78")
      (value "0R_0805")
      (footprint "eagle-import:R0805W")
      (libsource (lib "eagle-import") (part "0R_0805"))
    )
    (comp (ref "R79")
      (value "10K")
      (footprint "eagle-import:R0805W")
      (libsource (lib "eagle-import") (part "R-EU_R0805W"))
    )
    (comp (ref "R80")
      (value "0R_0805")
      (footprint "eagle-import:R0805W")
      (libsource (lib "eagle-import") (part "0R_0805"))
    )
    (comp (ref "R81")
      (value "0R_0805")
      (footprint "eagle-import:R0805W")
      (libsource (lib "eagle-import") (part "0R_0805"))
    )
    (comp (ref "R82")
      (value "0R_0805")
      (footprint "eagle-import:R0805W")
      (libsource (lib "eagle-import") (part "0R_0805"))
    )
    (comp (ref "R83")
      (value "0R_0805")
      (footprint "eagle-import:R0805W")
      (libsource (lib "eagle-import") (part "0R_0805"))
    )
    (comp (ref "R84")
      (value "0R_0805")
      (footprint "eagle-import:R0805W")
      (libsource (lib "eagle-import") (part "0R_0805"))
    )
    (comp (ref "R85")
      (value "DNP")
      (footprint "eagle-import:R0805W")
      (libsource (lib "eagle-import") (part "R-EU_R0805W"))
    )
    (comp (ref "R86")
      (value "10K")
      (footprint "eagle-import:R0805W")
      (libsource (lib "eagle-import") (part "R-EU_R0805W"))
    )
    (comp (ref "R87")
      (value "DNP")
      (footprint "eagle-import:R0805W")
      (libsource (lib "eagle-import") (part "R-EU_R0805W"))
    )
    (comp (ref "R88")
      (value "0R_0805")
      (footprint "eagle-import:R0805W")
      (libsource (lib "eagle-import") (part "0R_0805"))
    )
    (comp (ref "R89")
      (value "10K")
      (footprint "eagle-import:R0805W")
      (libsource (lib "eagle-import") (part "R-EU_R0805W"))
    )
    (comp (ref "R90")
      (value "DNP")
      (footprint "eagle-import:R0805W")
      (libsource (lib "eagle-import") (part "R-EU_R0805W"))
    )
    (comp (ref "R91")
      (value "0R_0805")
      (footprint "eagle-import:R0805W")
      (libsource (lib "eagle-import") (part "0R_0805"))
    )
    (comp (ref "R92")
      (value "47K")
      (footprint "eagle-import:R0805W")
      (libsource (lib "eagle-import") (part "R-EU_R0805W"))
    )
    (comp (ref "R93")
      (value "DNP")
      (footprint "eagle-import:R0805W")
      (libsource (lib "eagle-import") (part "R-EU_R0805W"))
    )
    (comp (ref "R94")
      (value "DNP")
      (footprint "eagle-import:R0805W")
      (libsource (lib "eagle-import") (part "R-EU_R0805W"))
    )
    (comp (ref "R95")
      (value "DNP")
      (footprint "eagle-import:R0805W")
      (libsource (lib "eagle-import") (part "R-EU_R0805W"))
    )
    (comp (ref "R96")
      (value "10K")
      (footprint "eagle-import:R0805W")
      (libsource (lib "eagle-import") (part "R-EU_R0805W"))
    )
    (comp (ref "R98")
      (value "4K7")
      (footprint "eagle-import:R0805W")
      (libsource (lib "eagle-import") (part "R-EU_R0805W"))
    )
    (comp (ref "R99")
      (value "4K7")
      (footprint "eagle-import:R0805W")
      (libsource (lib "eagle-import") (part "R-EU_R0805W"))
    )
    (comp (ref "R100")
      (value "DNP")
      (footprint "eagle-import:R0805W")
      (libsource (lib "eagle-import") (part "R-EU_R0805W"))
    )
    (comp (ref "R101")
      (value "1K")
      (footprint "eagle-import:R0805W")
      (libsource (lib "eagle-import") (part "R-EU_R0805W"))
    )
    (comp (ref "R102")
      (value "1K")
      (footprint "eagle-import:R0805W")
      (libsource (lib "eagle-import") (part "R-EU_R0805W"))
    )
    (comp (ref "R103")
      (value "100K")
      (footprint "eagle-import:R0805W")
      (libsource (lib "eagle-import") (part "R-EU_R0805W"))
    )
    (comp (ref "R104")
      (value "100K")
      (footprint "eagle-import:R0805W")
      (libsource (lib "eagle-import") (part "R-EU_R0805W"))
    )
    (comp (ref "R105")
      (value "DNP")
      (footprint "eagle-import:R0805W")
      (libsource (lib "eagle-import") (part "R-EU_R0805W"))
    )
    (comp (ref "R106")
      (value "DNP")
      (footprint "eagle-import:R0805W")
      (libsource (lib "eagle-import") (part "R-EU_R0805W"))
    )
    (comp (ref "R107")
      (value "100K")
      (footprint "eagle-import:R0805W")
      (libsource (lib "eagle-import") (part "R-EU_R0805W"))
    )
    (comp (ref "R108")
      (value "100K")
      (footprint "eagle-import:R0805W")
      (libsource (lib "eagle-import") (part "R-EU_R0805W"))
    )
    (comp (ref "R109")
      (value "DNP")
      (footprint "eagle-import:R0805W")
      (libsource (lib "eagle-import") (part "R-EU_R0805W"))
    )
    (comp (ref "R110")
      (value "DNP")
      (footprint "eagle-import:R0805W")
      (libsource (lib "eagle-import") (part "R-EU_R0805W"))
    )
    (comp (ref "R111")
      (value "DNP")
      (footprint "eagle-import:R0805W")
      (libsource (lib "eagle-import") (part "R-EU_R0805W"))
    )
    (comp (ref "R112")
      (value "DNP")
      (footprint "eagle-import:R0805W")
      (libsource (lib "eagle-import") (part "R-EU_R0805W"))
    )
    (comp (ref "R113")
      (value "0R_0805")
      (footprint "eagle-import:R0805W")
      (libsource (lib "eagle-import") (part "0R_0805"))
    )
    (comp (ref "R114")
      (value "0R_0805")
      (footprint "eagle-import:R0805W")
      (libsource (lib "eagle-import") (part "0R_0805"))
    )
    (comp (ref "U$7")
      (value "OSHW-LOGOM")
      (footprint "eagle-import:OSHW-LOGO-M")
      (libsource (lib "eagle-import") (part "OSHW-LOGOM"))
    )
    (comp (ref "X4")
      (value "input")
      (footprint "eagle-import:PAK100_2500-5-16")
      (fields (field (name "MPN") "D2516-5002-AR"))
      (libsource (lib "eagle-import") (part "2516-5"))
    )
    (comp (ref "X6")
      (value "2512-5")
      (footprint "eagle-import:PAK100_2500-5-12")
      (fields (field (name "MPN") "N2514-5002RB"))
      (libsource (lib "eagle-import") (part "2512-5"))
    )
  )
  (nets
    (net (code "1") (name "+5V") (class "Default")
      (node (ref "C101") (pin "+") (pinfunction "+_+") (pintype "passive"))
      (node (ref "C26") (pin "2") (pinfunction "2_2") (pintype "passive"))
      (node (ref "C28") (pin "2") (pinfunction "2_2") (pintype "passive"))
      (node (ref "C29") (pin "1") (pinfunction "1_1") (pintype "passive"))
      (node (ref "C30") (pin "1") (pinfunction "1_1") (pintype "passive"))
      (node (ref "C31") (pin "1") (pinfunction "1_1") (pintype "passive"))
      (node (ref "C32") (pin "2") (pinfunction "2_2") (pintype "passive"))
      (node (ref "C34") (pin "1") (pinfunction "1_1") (pintype "passive"))
      (node (ref "C35") (pin "1") (pinfunction "1_1") (pintype "passive"))
      (node (ref "C36") (pin "1") (pinfunction "1_1") (pintype "passive"))
      (node (ref "C37") (pin "1") (pinfunction "1_1") (pintype "passive"))
      (node (ref "C46") (pin "2") (pinfunction "2_2") (pintype "passive"))
      (node (ref "C48") (pin "1") (pinfunction "1_1") (pintype "passive"))
      (node (ref "C49") (pin "1") (pinfunction "1_1") (pintype "passive"))
      (node (ref "C51") (pin "2") (pinfunction "2_2") (pintype "passive"))
      (node (ref "C52") (pin "1") (pinfunction "1_1") (pintype "passive"))
      (node (ref "C58") (pin "2") (pinfunction "2_2") (pintype "passive"))
      (node (ref "C59") (pin "2") (pinfunction "2_2") (pintype "passive"))
      (node (ref "C60") (pin "2") (pinfunction "2_2") (pintype "passive"))
      (node (ref "C61") (pin "2") (pinfunction "2_2") (pintype "passive"))
      (node (ref "C62") (pin "2") (pinfunction "2_2") (pintype "passive"))
      (node (ref "C70") (pin "+") (pinfunction "+_+") (pintype "passive"))
      (node (ref "C76") (pin "+") (pinfunction "+_+") (pintype "passive"))
      (node (ref "C78") (pin "+") (pinfunction "+_+") (pintype "passive"))
      (node (ref "C88") (pin "+") (pinfunction "+_+") (pintype "passive"))
      (node (ref "C89") (pin "+") (pinfunction "+_+") (pintype "passive"))
      (node (ref "IC1") (pin "12") (pinfunction "VA+_12") (pintype "power_in"))
      (node (ref "IC14") (pin "12") (pinfunction "VA+_12") (pintype "power_in"))
      (node (ref "IC2") (pin "12") (pinfunction "VA+_12") (pintype "power_in"))
      (node (ref "IC3") (pin "12") (pinfunction "VA+_12") (pintype "power_in"))
      (node (ref "IC4") (pin "12") (pinfunction "VA+_12") (pintype "power_in"))
      (node (ref "IC5") (pin "12") (pinfunction "VA+_12") (pintype "power_in"))
      (node (ref "IC6") (pin "8") (pinfunction "V+_8") (pintype "power_in"))
      (node (ref "IC7") (pin "8") (pinfunction "V+_8") (pintype "power_in"))
      (node (ref "IC8") (pin "8") (pinfunction "V+_8") (pintype "power_in"))
      (node (ref "IC9") (pin "8") (pinfunction "V+_8") (pintype "power_in"))
      (node (ref "TP3") (pin "P$1") (pinfunction "1_P$1") (pintype "bidirectional"))
      (node (ref "U$6") (pin "P$2") (pinfunction "P$2_P$2") (pintype "bidirectional"))
    )
    (net (code "2") (name "+5V_PGA") (class "Default")
      (node (ref "C45") (pin "1") (pinfunction "1_1") (pintype "passive"))
      (node (ref "C47") (pin "1") (pinfunction "1_1") (pintype "passive"))
      (node (ref "C50") (pin "1") (pinfunction "1_1") (pintype "passive"))
      (node (ref "C57") (pin "2") (pinfunction "2_2") (pintype "passive"))
      (node (ref "C81") (pin "1") (pinfunction "1_1") (pintype "passive"))
      (node (ref "C82") (pin "1") (pinfunction "1_1") (pintype "passive"))
      (node (ref "C83") (pin "1") (pinfunction "1_1") (pintype "passive"))
      (node (ref "C91") (pin "+") (pinfunction "+_+") (pintype "passive"))
      (node (ref "C97") (pin "+") (pinfunction "+_+") (pintype "passive"))
      (node (ref "C98") (pin "+") (pinfunction "+_+") (pintype "passive"))
      (node (ref "C99") (pin "+") (pinfunction "+_+") (pintype "passive"))
      (node (ref "IC1") (pin "1") (pinfunction "ZCEN_1") (pintype "input"))
      (node (ref "IC1") (pin "4") (pinfunction "VD+_4") (pintype "power_in"))
      (node (ref "IC14") (pin "1") (pinfunction "ZCEN_1") (pintype "input"))
      (node (ref "IC14") (pin "4") (pinfunction "VD+_4") (pintype "power_in"))
      (node (ref "IC2") (pin "1") (pinfunction "ZCEN_1") (pintype "input"))
      (node (ref "IC2") (pin "4") (pinfunction "VD+_4") (pintype "power_in"))
      (node (ref "IC3") (pin "1") (pinfunction "ZCEN_1") (pintype "input"))
      (node (ref "IC3") (pin "4") (pinfunction "VD+_4") (pintype "power_in"))
      (node (ref "IC4") (pin "1") (pinfunction "ZCEN_1") (pintype "input"))
      (node (ref "IC4") (pin "4") (pinfunction "VD+_4") (pintype "power_in"))
      (node (ref "IC5") (pin "1") (pinfunction "ZCEN_1") (pintype "input"))
      (node (ref "IC5") (pin "4") (pinfunction "VD+_4") (pintype "power_in"))
      (node (ref "Q1") (pin "3") (pinfunction "D_3") (pintype "passive"))
      (node (ref "TP7") (pin "P$1") (pinfunction "1_P$1") (pintype "bidirectional"))
    )
    (net (code "3") (name "+5V{slash}1") (class "Default")
      (node (ref "C109") (pin "+") (pinfunction "+_+") (pintype "passive"))
      (node (ref "C71") (pin "2") (pinfunction "2_2") (pintype "passive"))
      (node (ref "C74") (pin "+") (pinfunction "+_+") (pintype "passive"))
      (node (ref "Q1") (pin "2") (pinfunction "S_2") (pintype "passive"))
      (node (ref "R37") (pin "2") (pinfunction "2_2") (pintype "passive"))
      (node (ref "TP5") (pin "P$1") (pinfunction "1_P$1") (pintype "bidirectional"))
      (node (ref "U$12") (pin "P$2") (pinfunction "P$2_P$2") (pintype "bidirectional"))
      (node (ref "U1") (pin "1") (pinfunction "IN_1") (pintype "input"))
      (node (ref "U1") (pin "3") (pinfunction "EN_3") (pintype "input"))
    )
    (net (code "4") (name "+15V") (class "Default")
      (node (ref "C103") (pin "+") (pinfunction "+_+") (pintype "passive"))
      (node (ref "C104") (pin "+") (pinfunction "+_+") (pintype "passive"))
      (node (ref "C105") (pin "+") (pinfunction "+_+") (pintype "passive"))
      (node (ref "C17") (pin "1") (pinfunction "1_1") (pintype "passive"))
      (node (ref "C18") (pin "1") (pinfunction "1_1") (pintype "passive"))
      (node (ref "C24") (pin "1") (pinfunction "1_1") (pintype "passive"))
      (node (ref "C25") (pin "1") (pinfunction "1_1") (pintype "passive"))
      (node (ref "C33") (pin "1") (pinfunction "1_1") (pintype "passive"))
      (node (ref "C63") (pin "1") (pinfunction "1_1") (pintype "passive"))
      (node (ref "C79") (pin "1") (pinfunction "1_1") (pintype "passive"))
      (node (ref "C80") (pin "1") (pinfunction "1_1") (pintype "passive"))
      (node (ref "C92") (pin "+") (pinfunction "+_+") (pintype "passive"))
      (node (ref "IC10") (pin "8") (pinfunction "V+_8") (pintype "power_in"))
      (node (ref "IC11") (pin "8") (pinfunction "V+_8") (pintype "power_in"))
      (node (ref "IC12") (pin "8") (pinfunction "V+_8") (pintype "power_in"))
      (node (ref "IC13") (pin "8") (pinfunction "V+_8") (pintype "power_in"))
      (node (ref "TP1") (pin "P$1") (pinfunction "1_P$1") (pintype "bidirectional"))
      (node (ref "U$2") (pin "P$2") (pinfunction "P$2_P$2") (pintype "bidirectional"))
    )
    (net (code "5") (name "-5V") (class "Default")
      (node (ref "C100") (pin "-") (pinfunction "-_-") (pintype "passive"))
      (node (ref "C108") (pin "-") (pinfunction "-_-") (pintype "passive"))
      (node (ref "C26") (pin "1") (pinfunction "1_1") (pintype "passive"))
      (node (ref "C28") (pin "1") (pinfunction "1_1") (pintype "passive"))
      (node (ref "C32") (pin "1") (pinfunction "1_1") (pintype "passive"))
      (node (ref "C38") (pin "1") (pinfunction "1_1") (pintype "passive"))
      (node (ref "C39") (pin "1") (pinfunction "1_1") (pintype "passive"))
      (node (ref "C40") (pin "1") (pinfunction "1_1") (pintype "passive"))
      (node (ref "C41") (pin "1") (pinfunction "1_1") (pintype "passive"))
      (node (ref "C42") (pin "1") (pinfunction "1_1") (pintype "passive"))
      (node (ref "C43") (pin "1") (pinfunction "1_1") (pintype "passive"))
      (node (ref "C44") (pin "1") (pinfunction "1_1") (pintype "passive"))
      (node (ref "C46") (pin "1") (pinfunction "1_1") (pintype "passive"))
      (node (ref "C51") (pin "1") (pinfunction "1_1") (pintype "passive"))
      (node (ref "C53") (pin "1") (pinfunction "1_1") (pintype "passive"))
      (node (ref "C54") (pin "1") (pinfunction "1_1") (pintype "passive"))
      (node (ref "C58") (pin "1") (pinfunction "1_1") (pintype "passive"))
      (node (ref "C59") (pin "1") (pinfunction "1_1") (pintype "passive"))
      (node (ref "C60") (pin "1") (pinfunction "1_1") (pintype "passive"))
      (node (ref "C61") (pin "1") (pinfunction "1_1") (pintype "passive"))
      (node (ref "C62") (pin "1") (pinfunction "1_1") (pintype "passive"))
      (node (ref "C64") (pin "1") (pinfunction "1_1") (pintype "passive"))
      (node (ref "C77") (pin "-") (pinfunction "-_-") (pintype "passive"))
      (node (ref "C90") (pin "-") (pinfunction "-_-") (pintype "passive"))
      (node (ref "C93") (pin "-") (pinfunction "-_-") (pintype "passive"))
      (node (ref "C94") (pin "-") (pinfunction "-_-") (pintype "passive"))
      (node (ref "C95") (pin "-") (pinfunction "-_-") (pintype "passive"))
      (node (ref "IC1") (pin "13") (pinfunction "VA-_13") (pintype "power_in"))
      (node (ref "IC14") (pin "13") (pinfunction "VA-_13") (pintype "power_in"))
      (node (ref "IC2") (pin "13") (pinfunction "VA-_13") (pintype "power_in"))
      (node (ref "IC3") (pin "13") (pinfunction "VA-_13") (pintype "power_in"))
      (node (ref "IC4") (pin "13") (pinfunction "VA-_13") (pintype "power_in"))
      (node (ref "IC5") (pin "13") (pinfunction "VA-_13") (pintype "power_in"))
      (node (ref "IC6") (pin "4") (pinfunction "V-_4") (pintype "power_in"))
      (node (ref "IC7") (pin "4") (pinfunction "V-_4") (pintype "power_in"))
      (node (ref "IC8") (pin "4") (pinfunction "V-_4") (pintype "power_in"))
      (node (ref "IC9") (pin "4") (pinfunction "V-_4") (pintype "power_in"))
      (node (ref "TP4") (pin "P$1") (pinfunction "1_P$1") (pintype "bidirectional"))
      (node (ref "U$9") (pin "P$2") (pinfunction "P$2_P$2") (pintype "bidirectional"))
    )
    (net (code "6") (name "-15V") (class "Default")
      (node (ref "C102") (pin "-") (pinfunction "-_-") (pintype "passive"))
      (node (ref "C106") (pin "-") (pinfunction "-_-") (pintype "passive"))
      (node (ref "C107") (pin "-") (pinfunction "-_-") (pintype "passive"))
      (node (ref "C19") (pin "1") (pinfunction "1_1") (pintype "passive"))
      (node (ref "C20") (pin "1") (pinfunction "1_1") (pintype "passive"))
      (node (ref "C21") (pin "1") (pinfunction "1_1") (pintype "passive"))
      (node (ref "C22") (pin "1") (pinfunction "1_1") (pintype "passive"))
      (node (ref "C33") (pin "2") (pinfunction "2_2") (pintype "passive"))
      (node (ref "C63") (pin "2") (pinfunction "2_2") (pintype "passive"))
      (node (ref "C79") (pin "2") (pinfunction "2_2") (pintype "passive"))
      (node (ref "C80") (pin "2") (pinfunction "2_2") (pintype "passive"))
      (node (ref "C96") (pin "-") (pinfunction "-_-") (pintype "passive"))
      (node (ref "IC10") (pin "4") (pinfunction "V-_4") (pintype "power_in"))
      (node (ref "IC11") (pin "4") (pinfunction "V-_4") (pintype "power_in"))
      (node (ref "IC12") (pin "4") (pinfunction "V-_4") (pintype "power_in"))
      (node (ref "IC13") (pin "4") (pinfunction "V-_4") (pintype "power_in"))
      (node (ref "TP2") (pin "P$1") (pinfunction "1_P$1") (pintype "bidirectional"))
      (node (ref "U$5") (pin "P$2") (pinfunction "P$2_P$2") (pintype "bidirectional"))
    )
    (net (code "7") (name "3V3") (class "Default")
      (node (ref "C72") (pin "2") (pinfunction "2_2") (pintype "passive"))
      (node (ref "C75") (pin "+") (pinfunction "+_+") (pintype "passive"))
      (node (ref "C84") (pin "1") (pinfunction "1_1") (pintype "passive"))
      (node (ref "C85") (pin "1") (pinfunction "1_1") (pintype "passive"))
      (node (ref "C86") (pin "1") (pinfunction "1_1") (pintype "passive"))
      (node (ref "C87") (pin "+") (pinfunction "+_+") (pintype "passive"))
      (node (ref "JP3") (pin "2") (pinfunction "2_2") (pintype "passive"))
      (node (ref "R34") (pin "2") (pinfunction "2_2") (pintype "passive"))
      (node (ref "TP6") (pin "P$1") (pinfunction "1_P$1") (pintype "bidirectional"))
      (node (ref "U$11") (pin "11") (pinfunction "11_11") (pintype "power_in"))
      (node (ref "U$11") (pin "28") (pinfunction "28_28") (pintype "power_in"))
      (node (ref "U$11") (pin "7") (pinfunction "7_7") (pintype "power_in"))
      (node (ref "U$13") (pin "P$2") (pinfunction "P$2_P$2") (pintype "bidirectional"))
      (node (ref "U1") (pin "5") (pinfunction "OUT_5") (pintype "passive"))
      (node (ref "X1") (pin "4") (pinfunction "4_4") (pintype "passive"))
      (node (ref "X3") (pin "1") (pinfunction "1_1") (pintype "passive"))
    )
    (net (code "8") (name "42") (class "Default")
      (node (ref "U$11") (pin "42") (pinfunction "42_42") (pintype "power_in"))
    )
    (net (code "9") (name "43") (class "Default")
      (node (ref "U$11") (pin "43") (pinfunction "43_43") (pintype "power_in"))
    )
    (net (code "10") (name "46") (class "Default")
      (node (ref "U$11") (pin "46") (pinfunction "46_46") (pintype "power_in"))
    )
    (net (code "11") (name "AGND") (class "Default")
      (node (ref "C100") (pin "+") (pinfunction "+_+") (pintype "passive"))
      (node (ref "C101") (pin "-") (pinfunction "-_-") (pintype "passive"))
      (node (ref "C102") (pin "+") (pinfunction "+_+") (pintype "passive"))
      (node (ref "C103") (pin "-") (pinfunction "-_-") (pintype "passive"))
      (node (ref "C104") (pin "-") (pinfunction "-_-") (pintype "passive"))
      (node (ref "C105") (pin "-") (pinfunction "-_-") (pintype "passive"))
      (node (ref "C106") (pin "+") (pinfunction "+_+") (pintype "passive"))
      (node (ref "C107") (pin "+") (pinfunction "+_+") (pintype "passive"))
      (node (ref "C108") (pin "+") (pinfunction "+_+") (pintype "passive"))
      (node (ref "C11") (pin "1") (pinfunction "1_1") (pintype "passive"))
      (node (ref "C12") (pin "1") (pinfunction "1_1") (pintype "passive"))
      (node (ref "C15") (pin "1") (pinfunction "1_1") (pintype "passive"))
      (node (ref "C16") (pin "1") (pinfunction "1_1") (pintype "passive"))
      (node (ref "C17") (pin "2") (pinfunction "2_2") (pintype "passive"))
      (node (ref "C18") (pin "2") (pinfunction "2_2") (pintype "passive"))
      (node (ref "C19") (pin "2") (pinfunction "2_2") (pintype "passive"))
      (node (ref "C20") (pin "2") (pinfunction "2_2") (pintype "passive"))
      (node (ref "C21") (pin "2") (pinfunction "2_2") (pintype "passive"))
      (node (ref "C22") (pin "2") (pinfunction "2_2") (pintype "passive"))
      (node (ref "C24") (pin "2") (pinfunction "2_2") (pintype "passive"))
      (node (ref "C25") (pin "2") (pinfunction "2_2") (pintype "passive"))
      (node (ref "C29") (pin "2") (pinfunction "2_2") (pintype "passive"))
      (node (ref "C3") (pin "1") (pinfunction "1_1") (pintype "passive"))
      (node (ref "C30") (pin "2") (pinfunction "2_2") (pintype "passive"))
      (node (ref "C31") (pin "2") (pinfunction "2_2") (pintype "passive"))
      (node (ref "C34") (pin "2") (pinfunction "2_2") (pintype "passive"))
      (node (ref "C35") (pin "2") (pinfunction "2_2") (pintype "passive"))
      (node (ref "C36") (pin "2") (pinfunction "2_2") (pintype "passive"))
      (node (ref "C37") (pin "2") (pinfunction "2_2") (pintype "passive"))
      (node (ref "C38") (pin "2") (pinfunction "2_2") (pintype "passive"))
      (node (ref "C39") (pin "2") (pinfunction "2_2") (pintype "passive"))
      (node (ref "C4") (pin "1") (pinfunction "1_1") (pintype "passive"))
      (node (ref "C40") (pin "2") (pinfunction "2_2") (pintype "passive"))
      (node (ref "C41") (pin "2") (pinfunction "2_2") (pintype "passive"))
      (node (ref "C42") (pin "2") (pinfunction "2_2") (pintype "passive"))
      (node (ref "C43") (pin "2") (pinfunction "2_2") (pintype "passive"))
      (node (ref "C44") (pin "2") (pinfunction "2_2") (pintype "passive"))
      (node (ref "C48") (pin "2") (pinfunction "2_2") (pintype "passive"))
      (node (ref "C49") (pin "2") (pinfunction "2_2") (pintype "passive"))
      (node (ref "C52") (pin "2") (pinfunction "2_2") (pintype "passive"))
      (node (ref "C53") (pin "2") (pinfunction "2_2") (pintype "passive"))
      (node (ref "C54") (pin "2") (pinfunction "2_2") (pintype "passive"))
      (node (ref "C64") (pin "2") (pinfunction "2_2") (pintype "passive"))
      (node (ref "C65") (pin "1") (pinfunction "1_1") (pintype "passive"))
      (node (ref "C66") (pin "1") (pinfunction "1_1") (pintype "passive"))
      (node (ref "C7") (pin "1") (pinfunction "1_1") (pintype "passive"))
      (node (ref "C70") (pin "-") (pinfunction "-_-") (pintype "passive"))
      (node (ref "C76") (pin "-") (pinfunction "-_-") (pintype "passive"))
      (node (ref "C77") (pin "+") (pinfunction "+_+") (pintype "passive"))
      (node (ref "C78") (pin "-") (pinfunction "-_-") (pintype "passive"))
      (node (ref "C8") (pin "1") (pinfunction "1_1") (pintype "passive"))
      (node (ref "C88") (pin "-") (pinfunction "-_-") (pintype "passive"))
      (node (ref "C89") (pin "-") (pinfunction "-_-") (pintype "passive"))
      (node (ref "C90") (pin "+") (pinfunction "+_+") (pintype "passive"))
      (node (ref "C92") (pin "-") (pinfunction "-_-") (pintype "passive"))
      (node (ref "C93") (pin "+") (pinfunction "+_+") (pintype "passive"))
      (node (ref "C94") (pin "+") (pinfunction "+_+") (pintype "passive"))
      (node (ref "C95") (pin "+") (pinfunction "+_+") (pintype "passive"))
      (node (ref "C96") (pin "+") (pinfunction "+_+") (pintype "passive"))
      (node (ref "IC1") (pin "10") (pinfunction "AGNDR_10") (pintype "power_in"))
      (node (ref "IC1") (pin "15") (pinfunction "AGNDL_15") (pintype "power_in"))
      (node (ref "IC14") (pin "10") (pinfunction "AGNDR_10") (pintype "power_in"))
      (node (ref "IC14") (pin "15") (pinfunction "AGNDL_15") (pintype "power_in"))
      (node (ref "IC2") (pin "10") (pinfunction "AGNDR_10") (pintype "power_in"))
      (node (ref "IC2") (pin "15") (pinfunction "AGNDL_15") (pintype "power_in"))
      (node (ref "IC3") (pin "10") (pinfunction "AGNDR_10") (pintype "power_in"))
      (node (ref "IC3") (pin "15") (pinfunction "AGNDL_15") (pintype "power_in"))
      (node (ref "IC4") (pin "10") (pinfunction "AGNDR_10") (pintype "power_in"))
      (node (ref "IC4") (pin "15") (pinfunction "AGNDL_15") (pintype "power_in"))
      (node (ref "IC5") (pin "10") (pinfunction "AGNDR_10") (pintype "power_in"))
      (node (ref "IC5") (pin "15") (pinfunction "AGNDL_15") (pintype "power_in"))
      (node (ref "R1") (pin "1") (pinfunction "1_1") (pintype "passive"))
      (node (ref "R100") (pin "1") (pinfunction "1_1") (pintype "passive"))
      (node (ref "R103") (pin "1") (pinfunction "1_1") (pintype "passive"))
      (node (ref "R104") (pin "1") (pinfunction "1_1") (pintype "passive"))
      (node (ref "R105") (pin "1") (pinfunction "1_1") (pintype "passive"))
      (node (ref "R106") (pin "1") (pinfunction "1_1") (pintype "passive"))
      (node (ref "R107") (pin "1") (pinfunction "1_1") (pintype "passive"))
      (node (ref "R108") (pin "1") (pinfunction "1_1") (pintype "passive"))
      (node (ref "R109") (pin "1") (pinfunction "1_1") (pintype "passive"))
      (node (ref "R11") (pin "1") (pinfunction "1_1") (pintype "passive"))
      (node (ref "R110") (pin "1") (pinfunction "1_1") (pintype "passive"))
      (node (ref "R111") (pin "1") (pinfunction "1_1") (pintype "passive"))
      (node (ref "R112") (pin "1") (pinfunction "1_1") (pintype "passive"))
      (node (ref "R113") (pin "1") (pinfunction "P$1_1") (pintype "bidirectional"))
      (node (ref "R13") (pin "1") (pinfunction "1_1") (pintype "passive"))
      (node (ref "R14") (pin "1") (pinfunction "1_1") (pintype "passive"))
      (node (ref "R15") (pin "1") (pinfunction "1_1") (pintype "passive"))
      (node (ref "R16") (pin "1") (pinfunction "1_1") (pintype "passive"))
      (node (ref "R17") (pin "1") (pinfunction "1_1") (pintype "passive"))
      (node (ref "R23") (pin "1") (pinfunction "1_1") (pintype "passive"))
      (node (ref "R29") (pin "1") (pinfunction "1_1") (pintype "passive"))
      (node (ref "R3") (pin "1") (pinfunction "1_1") (pintype "passive"))
      (node (ref "R35") (pin "1") (pinfunction "1_1") (pintype "passive"))
      (node (ref "R41") (pin "1") (pinfunction "1_1") (pintype "passive"))
      (node (ref "R43") (pin "1") (pinfunction "1_1") (pintype "passive"))
      (node (ref "R5") (pin "1") (pinfunction "1_1") (pintype "passive"))
      (node (ref "R52") (pin "1") (pinfunction "1_1") (pintype "passive"))
      (node (ref "R53") (pin "1") (pinfunction "1_1") (pintype "passive"))
      (node (ref "R54") (pin "1") (pinfunction "1_1") (pintype "passive"))
      (node (ref "R55") (pin "1") (pinfunction "1_1") (pintype "passive"))
      (node (ref "R56") (pin "1") (pinfunction "1_1") (pintype "passive"))
      (node (ref "R57") (pin "1") (pinfunction "1_1") (pintype "passive"))
      (node (ref "R58") (pin "1") (pinfunction "1_1") (pintype "passive"))
      (node (ref "R59") (pin "1") (pinfunction "1_1") (pintype "passive"))
      (node (ref "R60") (pin "1") (pinfunction "1_1") (pintype "passive"))
      (node (ref "R61") (pin "1") (pinfunction "1_1") (pintype "passive"))
      (node (ref "R62") (pin "1") (pinfunction "1_1") (pintype "passive"))
      (node (ref "R63") (pin "1") (pinfunction "1_1") (pintype "passive"))
      (node (ref "R67") (pin "1") (pinfunction "1_1") (pintype "passive"))
      (node (ref "R7") (pin "1") (pinfunction "1_1") (pintype "passive"))
      (node (ref "R70") (pin "1") (pinfunction "1_1") (pintype "passive"))
      (node (ref "R73") (pin "1") (pinfunction "1_1") (pintype "passive"))
      (node (ref "R75") (pin "2") (pinfunction "2_2") (pintype "passive"))
      (node (ref "R76") (pin "1") (pinfunction "1_1") (pintype "passive"))
      (node (ref "R85") (pin "2") (pinfunction "2_2") (pintype "passive"))
      (node (ref "R87") (pin "2") (pinfunction "2_2") (pintype "passive"))
      (node (ref "R9") (pin "1") (pinfunction "1_1") (pintype "passive"))
      (node (ref "R90") (pin "2") (pinfunction "2_2") (pintype "passive"))
      (node (ref "R93") (pin "1") (pinfunction "1_1") (pintype "passive"))
      (node (ref "R94") (pin "1") (pinfunction "1_1") (pintype "passive"))
      (node (ref "R95") (pin "1") (pinfunction "1_1") (pintype "passive"))
      (node (ref "R98") (pin "1") (pinfunction "1_1") (pintype "passive"))
      (node (ref "R99") (pin "1") (pinfunction "1_1") (pintype "passive"))
      (node (ref "X4") (pin "1") (pinfunction "KL_1") (pintype "passive"))
      (node (ref "X4") (pin "10") (pinfunction "KL_10") (pintype "passive"))
      (node (ref "X4") (pin "13") (pinfunction "KL_13") (pintype "passive"))
      (node (ref "X4") (pin "15") (pinfunction "KL_15") (pintype "passive"))
      (node (ref "X4") (pin "4") (pinfunction "KL_4") (pintype "passive"))
      (node (ref "X4") (pin "7") (pinfunction "KL_7") (pintype "passive"))
      (node (ref "X5") (pin "2") (pinfunction "KL_2") (pintype "passive"))
      (node (ref "X5") (pin "4") (pinfunction "KL_4") (pintype "passive"))
      (node (ref "X5") (pin "6") (pinfunction "KL_6") (pintype "passive"))
      (node (ref "X5") (pin "8") (pinfunction "KL_8") (pintype "passive"))
      (node (ref "X6") (pin "10") (pinfunction "KL_10") (pintype "passive"))
      (node (ref "X6") (pin "12") (pinfunction "KL_12") (pintype "passive"))
      (node (ref "X6") (pin "2") (pinfunction "KL_2") (pintype "passive"))
      (node (ref "X6") (pin "4") (pinfunction "KL_4") (pintype "passive"))
      (node (ref "X6") (pin "6") (pinfunction "KL_6") (pintype "passive"))
      (node (ref "X6") (pin "8") (pinfunction "KL_8") (pintype "passive"))
    )
    (net (code "12") (name "CENTER") (class "Default")
      (node (ref "C67") (pin "1") (pinfunction "1_1") (pintype "passive"))
      (node (ref "R103") (pin "2") (pinfunction "2_2") (pintype "passive"))
      (node (ref "X4") (pin "14") (pinfunction "KL_14") (pintype "passive"))
    )
    (net (code "13") (name "CLK") (class "Default")
      (node (ref "IC1") (pin "6") (pinfunction "SCLK_6") (pintype "input"))
      (node (ref "IC14") (pin "6") (pinfunction "SCLK_6") (pintype "input"))
      (node (ref "IC2") (pin "6") (pinfunction "SCLK_6") (pintype "input"))
      (node (ref "IC3") (pin "6") (pinfunction "SCLK_6") (pintype "input"))
      (node (ref "IC4") (pin "6") (pinfunction "SCLK_6") (pintype "input"))
      (node (ref "IC5") (pin "6") (pinfunction "SCLK_6") (pintype "input"))
      (node (ref "U$11") (pin "32") (pinfunction "32_32") (pintype "bidirectional"))
    )
    (net (code "14") (name "CS1") (class "Default")
      (node (ref "IC1") (pin "2") (pinfunction "CS_2") (pintype "input"))
      (node (ref "U$11") (pin "36") (pinfunction "36_36") (pintype "bidirectional"))
    )
    (net (code "15") (name "CS2") (class "Default")
      (node (ref "IC2") (pin "2") (pinfunction "CS_2") (pintype "input"))
      (node (ref "U$11") (pin "20") (pinfunction "20_20") (pintype "bidirectional"))
    )
    (net (code "16") (name "CS3") (class "Default")
      (node (ref "IC3") (pin "2") (pinfunction "CS_2") (pintype "input"))
      (node (ref "U$11") (pin "31") (pinfunction "31_31") (pintype "bidirectional"))
    )
    (net (code "17") (name "CS4") (class "Default")
      (node (ref "IC4") (pin "2") (pinfunction "CS_2") (pintype "input"))
      (node (ref "U$11") (pin "22") (pinfunction "22_22") (pintype "bidirectional"))
    )
    (net (code "18") (name "CS5") (class "Default")
      (node (ref "IC5") (pin "2") (pinfunction "CS_2") (pintype "input"))
      (node (ref "U$11") (pin "18") (pinfunction "18_18") (pintype "bidirectional"))
    )
    (net (code "19") (name "CS6") (class "Default")
      (node (ref "IC14") (pin "2") (pinfunction "CS_2") (pintype "input"))
      (node (ref "U$11") (pin "16") (pinfunction "16_16") (pintype "bidirectional"))
    )
    (net (code "20") (name "DGND") (class "Default")
      (node (ref "C109") (pin "-") (pinfunction "-_-") (pintype "passive"))
      (node (ref "C23") (pin "2") (pinfunction "2_2") (pintype "passive"))
      (node (ref "C45") (pin "2") (pinfunction "2_2") (pintype "passive"))
      (node (ref "C47") (pin "2") (pinfunction "2_2") (pintype "passive"))
      (node (ref "C50") (pin "2") (pinfunction "2_2") (pintype "passive"))
      (node (ref "C55") (pin "2") (pinfunction "2_2") (pintype "passive"))
      (node (ref "C56") (pin "2") (pinfunction "2_2") (pintype "passive"))
      (node (ref "C71") (pin "1") (pinfunction "1_1") (pintype "passive"))
      (node (ref "C72") (pin "1") (pinfunction "1_1") (pintype "passive"))
      (node (ref "C73") (pin "1") (pinfunction "1_1") (pintype "passive"))
      (node (ref "C74") (pin "-") (pinfunction "-_-") (pintype "passive"))
      (node (ref "C75") (pin "-") (pinfunction "-_-") (pintype "passive"))
      (node (ref "C81") (pin "2") (pinfunction "2_2") (pintype "passive"))
      (node (ref "C82") (pin "2") (pinfunction "2_2") (pintype "passive"))
      (node (ref "C83") (pin "2") (pinfunction "2_2") (pintype "passive"))
      (node (ref "C84") (pin "2") (pinfunction "2_2") (pintype "passive"))
      (node (ref "C85") (pin "2") (pinfunction "2_2") (pintype "passive"))
      (node (ref "C86") (pin "2") (pinfunction "2_2") (pintype "passive"))
      (node (ref "C87") (pin "-") (pinfunction "-_-") (pintype "passive"))
      (node (ref "C91") (pin "-") (pinfunction "-_-") (pintype "passive"))
      (node (ref "C97") (pin "-") (pinfunction "-_-") (pintype "passive"))
      (node (ref "C98") (pin "-") (pinfunction "-_-") (pintype "passive"))
      (node (ref "C99") (pin "-") (pinfunction "-_-") (pintype "passive"))
      (node (ref "IC1") (pin "5") (pinfunction "DGND_5") (pintype "power_in"))
      (node (ref "IC14") (pin "5") (pinfunction "DGND_5") (pintype "power_in"))
      (node (ref "IC2") (pin "5") (pinfunction "DGND_5") (pintype "power_in"))
      (node (ref "IC3") (pin "5") (pinfunction "DGND_5") (pintype "power_in"))
      (node (ref "IC4") (pin "5") (pinfunction "DGND_5") (pintype "power_in"))
      (node (ref "IC5") (pin "5") (pinfunction "DGND_5") (pintype "power_in"))
      (node (ref "R113") (pin "2") (pinfunction "P$2_2") (pintype "bidirectional"))
      (node (ref "R31") (pin "2") (pinfunction "2_2") (pintype "passive"))
      (node (ref "R33") (pin "1") (pinfunction "1_1") (pintype "passive"))
      (node (ref "R38") (pin "1") (pinfunction "1_1") (pintype "passive"))
      (node (ref "R47") (pin "2") (pinfunction "2_2") (pintype "passive"))
      (node (ref "R48") (pin "2") (pinfunction "2_2") (pintype "passive"))
      (node (ref "R49") (pin "2") (pinfunction "2_2") (pintype "passive"))
      (node (ref "R50") (pin "2") (pinfunction "2_2") (pintype "passive"))
      (node (ref "R51") (pin "2") (pinfunction "2_2") (pintype "passive"))
      (node (ref "R92") (pin "2") (pinfunction "2_2") (pintype "passive"))
      (node (ref "T1") (pin "2") (pinfunction "E_2") (pintype "passive"))
      (node (ref "U$11") (pin "10") (pinfunction "10_10") (pintype "power_in"))
      (node (ref "U$11") (pin "12") (pinfunction "12_12") (pintype "power_in"))
      (node (ref "U$11") (pin "27") (pinfunction "27_27") (pintype "power_in"))
      (node (ref "U$11") (pin "37") (pinfunction "37_37") (pintype "power_in"))
      (node (ref "U$11") (pin "39") (pinfunction "39_39") (pintype "bidirectional"))
      (node (ref "U$11") (pin "41") (pinfunction "41_41") (pintype "power_in"))
      (node (ref "U$11") (pin "44") (pinfunction "44_44") (pintype "power_in"))
      (node (ref "U1") (pin "2") (pinfunction "GND_2") (pintype "input"))
      (node (ref "X1") (pin "1") (pinfunction "1_1") (pintype "passive"))
      (node (ref "X3") (pin "4") (pinfunction "4_4") (pintype "passive"))
      (node (ref "X5") (pin "10") (pinfunction "KL_10") (pintype "passive"))
      (node (ref "X5") (pin "12") (pinfunction "KL_12") (pintype "passive"))
    )
    (net (code "21") (name "FRONT_L") (class "Default")
      (node (ref "C1") (pin "1") (pinfunction "1_1") (pintype "passive"))
      (node (ref "R60") (pin "2") (pinfunction "2_2") (pintype "passive"))
      (node (ref "X4") (pin "2") (pinfunction "KL_2") (pintype "passive"))
    )
    (net (code "22") (name "FRONT_R") (class "Default")
      (node (ref "C2") (pin "1") (pinfunction "1_1") (pintype "passive"))
      (node (ref "R61") (pin "2") (pinfunction "2_2") (pintype "passive"))
      (node (ref "X4") (pin "3") (pinfunction "KL_3") (pintype "passive"))
    )
    (net (code "23") (name "LINE_L") (class "Default")
      (node (ref "C9") (pin "1") (pinfunction "1_1") (pintype "passive"))
      (node (ref "R54") (pin "2") (pinfunction "2_2") (pintype "passive"))
      (node (ref "X4") (pin "5") (pinfunction "KL_5") (pintype "passive"))
    )
    (net (code "24") (name "LINE_R") (class "Default")
      (node (ref "C10") (pin "1") (pinfunction "1_1") (pintype "passive"))
      (node (ref "R55") (pin "2") (pinfunction "2_2") (pintype "passive"))
      (node (ref "X4") (pin "6") (pinfunction "KL_6") (pintype "passive"))
    )
    (net (code "25") (name "M1") (class "Default")
      (node (ref "IC1") (pin "8") (pinfunction "MUTE_8") (pintype "input"))
      (node (ref "U$11") (pin "35") (pinfunction "35_35") (pintype "bidirectional"))
    )
    (net (code "26") (name "M2") (class "Default")
      (node (ref "IC2") (pin "8") (pinfunction "MUTE_8") (pintype "input"))
      (node (ref "U$11") (pin "19") (pinfunction "19_19") (pintype "bidirectional"))
    )
    (net (code "27") (name "M3") (class "Default")
      (node (ref "IC3") (pin "8") (pinfunction "MUTE_8") (pintype "input"))
      (node (ref "U$11") (pin "29") (pinfunction "29_29") (pintype "bidirectional"))
    )
    (net (code "28") (name "M4") (class "Default")
      (node (ref "IC4") (pin "8") (pinfunction "MUTE_8") (pintype "input"))
      (node (ref "U$11") (pin "21") (pinfunction "21_21") (pintype "bidirectional"))
    )
    (net (code "29") (name "M5") (class "Default")
      (node (ref "IC5") (pin "8") (pinfunction "MUTE_8") (pintype "input"))
      (node (ref "U$11") (pin "17") (pinfunction "17_17") (pintype "bidirectional"))
    )
    (net (code "30") (name "M6") (class "Default")
      (node (ref "IC14") (pin "8") (pinfunction "MUTE_8") (pintype "input"))
      (node (ref "U$11") (pin "15") (pinfunction "15_15") (pintype "bidirectional"))
    )
    (net (code "31") (name "MOSI") (class "Default")
      (node (ref "IC1") (pin "3") (pinfunction "SDI_3") (pintype "input"))
      (node (ref "IC14") (pin "3") (pinfunction "SDI_3") (pintype "input"))
      (node (ref "IC2") (pin "3") (pinfunction "SDI_3") (pintype "input"))
      (node (ref "IC3") (pin "3") (pinfunction "SDI_3") (pintype "input"))
      (node (ref "IC4") (pin "3") (pinfunction "SDI_3") (pintype "input"))
      (node (ref "IC5") (pin "3") (pinfunction "SDI_3") (pintype "input"))
      (node (ref "U$11") (pin "30") (pinfunction "30_30") (pintype "bidirectional"))
    )
    (net (code "32") (name "M_CENTER") (class "Default")
      (node (ref "IC14") (pin "14") (pinfunction "VOUTL_14") (pintype "output"))
      (node (ref "X6") (pin "9") (pinfunction "KL_9") (pintype "passive"))
    )
    (net (code "33") (name "M_FRONT_L") (class "Default")
      (node (ref "IC10") (pin "7") (pinfunction "OUT_7") (pintype "output"))
      (node (ref "JP1") (pin "3") (pinfunction "3_3") (pintype "passive"))
      (node (ref "JP2") (pin "1") (pinfunction "1_1") (pintype "passive"))
      (node (ref "R68") (pin "1") (pinfunction "1_1") (pintype "passive"))
      (node (ref "X6") (pin "3") (pinfunction "KL_3") (pintype "passive"))
    )
    (net (code "34") (name "M_FRONT_R") (class "Default")
      (node (ref "IC11") (pin "7") (pinfunction "OUT_7") (pintype "output"))
      (node (ref "JP1") (pin "1") (pinfunction "1_1") (pintype "passive"))
      (node (ref "JP2") (pin "3") (pinfunction "3_3") (pintype "passive"))
      (node (ref "R71") (pin "1") (pinfunction "1_1") (pintype "passive"))
      (node (ref "X6") (pin "1") (pinfunction "KL_1") (pintype "passive"))
    )
    (net (code "35") (name "M_REAR_L") (class "Default")
      (node (ref "IC12") (pin "7") (pinfunction "OUT_7") (pintype "output"))
      (node (ref "R74") (pin "1") (pinfunction "1_1") (pintype "passive"))
      (node (ref "X6") (pin "7") (pinfunction "KL_7") (pintype "passive"))
    )
    (net (code "36") (name "M_REAR_R") (class "Default")
      (node (ref "IC13") (pin "7") (pinfunction "OUT_7") (pintype "output"))
      (node (ref "R77") (pin "1") (pinfunction "1_1") (pintype "passive"))
      (node (ref "X6") (pin "5") (pinfunction "KL_5") (pintype "passive"))
    )
    (net (code "37") (name "M_SW") (class "Default")
      (node (ref "IC14") (pin "11") (pinfunction "VOUTR_11") (pintype "output"))
      (node (ref "X6") (pin "11") (pinfunction "KL_11") (pintype "passive"))
    )
    (net (code "38") (name "Net-(C1-Pad2)") (class "Default")
      (node (ref "C1") (pin "2") (pinfunction "2_2") (pintype "passive"))
      (node (ref "R1") (pin "2") (pinfunction "2_2") (pintype "passive"))
      (node (ref "R42") (pin "1") (pinfunction "1_1") (pintype "passive"))
    )
    (net (code "39") (name "Net-(C2-Pad2)") (class "Default")
      (node (ref "C2") (pin "2") (pinfunction "2_2") (pintype "passive"))
      (node (ref "R3") (pin "2") (pinfunction "2_2") (pintype "passive"))
      (node (ref "R44") (pin "1") (pinfunction "1_1") (pintype "passive"))
    )
    (net (code "40") (name "Net-(C5-Pad2)") (class "Default")
      (node (ref "C5") (pin "2") (pinfunction "2_2") (pintype "passive"))
      (node (ref "R2") (pin "1") (pinfunction "1_1") (pintype "passive"))
      (node (ref "R5") (pin "2") (pinfunction "2_2") (pintype "passive"))
    )
    (net (code "41") (name "Net-(C6-Pad2)") (class "Default")
      (node (ref "C6") (pin "2") (pinfunction "2_2") (pintype "passive"))
      (node (ref "R4") (pin "1") (pinfunction "1_1") (pintype "passive"))
      (node (ref "R7") (pin "2") (pinfunction "2_2") (pintype "passive"))
    )
    (net (code "42") (name "Net-(C9-Pad2)") (class "Default")
      (node (ref "C9") (pin "2") (pinfunction "2_2") (pintype "passive"))
      (node (ref "R6") (pin "1") (pinfunction "1_1") (pintype "passive"))
      (node (ref "R9") (pin "2") (pinfunction "2_2") (pintype "passive"))
    )
    (net (code "43") (name "Net-(C10-Pad2)") (class "Default")
      (node (ref "C10") (pin "2") (pinfunction "2_2") (pintype "passive"))
      (node (ref "R11") (pin "2") (pinfunction "2_2") (pintype "passive"))
      (node (ref "R8") (pin "1") (pinfunction "1_1") (pintype "passive"))
    )
    (net (code "44") (name "Net-(C13-Pad2)") (class "Default")
      (node (ref "C13") (pin "2") (pinfunction "2_2") (pintype "passive"))
      (node (ref "R10") (pin "1") (pinfunction "1_1") (pintype "passive"))
      (node (ref "R13") (pin "2") (pinfunction "2_2") (pintype "passive"))
    )
    (net (code "45") (name "Net-(C14-Pad2)") (class "Default")
      (node (ref "C14") (pin "2") (pinfunction "2_2") (pintype "passive"))
      (node (ref "R12") (pin "1") (pinfunction "1_1") (pintype "passive"))
      (node (ref "R14") (pin "2") (pinfunction "2_2") (pintype "passive"))
    )
    (net (code "46") (name "Net-(C23-Pad1)") (class "Default")
      (node (ref "C23") (pin "1") (pinfunction "1_1") (pintype "passive"))
      (node (ref "U$11") (pin "13") (pinfunction "13_13") (pintype "power_in"))
    )
    (net (code "47") (name "Net-(C67-Pad2)") (class "Default")
      (node (ref "C67") (pin "2") (pinfunction "2_2") (pintype "passive"))
      (node (ref "R101") (pin "1") (pinfunction "1_1") (pintype "passive"))
      (node (ref "R105") (pin "2") (pinfunction "2_2") (pintype "passive"))
    )
    (net (code "48") (name "Net-(C68-Pad2)") (class "Default")
      (node (ref "C68") (pin "2") (pinfunction "2_2") (pintype "passive"))
      (node (ref "R102") (pin "1") (pinfunction "1_1") (pintype "passive"))
      (node (ref "R106") (pin "2") (pinfunction "2_2") (pintype "passive"))
    )
    (net (code "49") (name "Net-(IC1-SDO)") (class "Default")
      (node (ref "IC1") (pin "7") (pinfunction "SDO_7") (pintype "output"))
      (node (ref "R49") (pin "1") (pinfunction "1_1") (pintype "passive"))
    )
    (net (code "50") (name "Net-(IC1-VINL)") (class "Default")
      (node (ref "IC1") (pin "16") (pinfunction "VINL_16") (pintype "input"))
      (node (ref "IC6") (pin "1") (pinfunction "OUT_1") (pintype "output"))
      (node (ref "R109") (pin "2") (pinfunction "2_2") (pintype "passive"))
      (node (ref "R64") (pin "1") (pinfunction "P$1_1") (pintype "bidirectional"))
    )
    (net (code "51") (name "Net-(IC1-VINR)") (class "Default")
      (node (ref "IC1") (pin "9") (pinfunction "VINR_9") (pintype "input"))
      (node (ref "IC6") (pin "7") (pinfunction "OUT_7") (pintype "output"))
      (node (ref "R65") (pin "1") (pinfunction "P$1_1") (pintype "bidirectional"))
      (node (ref "R94") (pin "2") (pinfunction "2_2") (pintype "passive"))
    )
    (net (code "52") (name "Net-(IC2-SDO)") (class "Default")
      (node (ref "IC2") (pin "7") (pinfunction "SDO_7") (pintype "output"))
      (node (ref "R48") (pin "1") (pinfunction "1_1") (pintype "passive"))
    )
    (net (code "53") (name "Net-(IC2-VINL)") (class "Default")
      (node (ref "IC2") (pin "16") (pinfunction "VINL_16") (pintype "input"))
      (node (ref "IC7") (pin "1") (pinfunction "OUT_1") (pintype "output"))
      (node (ref "R112") (pin "2") (pinfunction "2_2") (pintype "passive"))
      (node (ref "R114") (pin "1") (pinfunction "P$1_1") (pintype "bidirectional"))
    )
    (net (code "54") (name "Net-(IC2-VINR)") (class "Default")
      (node (ref "IC2") (pin "9") (pinfunction "VINR_9") (pintype "input"))
      (node (ref "IC7") (pin "7") (pinfunction "OUT_7") (pintype "output"))
      (node (ref "R100") (pin "2") (pinfunction "2_2") (pintype "passive"))
      (node (ref "R66") (pin "1") (pinfunction "P$1_1") (pintype "bidirectional"))
    )
    (net (code "55") (name "Net-(IC3-SDO)") (class "Default")
      (node (ref "IC3") (pin "7") (pinfunction "SDO_7") (pintype "output"))
      (node (ref "R47") (pin "1") (pinfunction "1_1") (pintype "passive"))
    )
    (net (code "56") (name "Net-(IC3-VINL)") (class "Default")
      (node (ref "IC3") (pin "16") (pinfunction "VINL_16") (pintype "input"))
      (node (ref "IC8") (pin "1") (pinfunction "OUT_1") (pintype "output"))
      (node (ref "R110") (pin "2") (pinfunction "2_2") (pintype "passive"))
      (node (ref "R80") (pin "1") (pinfunction "P$1_1") (pintype "bidirectional"))
    )
    (net (code "57") (name "Net-(IC3-VINR)") (class "Default")
      (node (ref "IC3") (pin "9") (pinfunction "VINR_9") (pintype "input"))
      (node (ref "IC8") (pin "7") (pinfunction "OUT_7") (pintype "output"))
      (node (ref "R81") (pin "1") (pinfunction "P$1_1") (pintype "bidirectional"))
      (node (ref "R95") (pin "2") (pinfunction "2_2") (pintype "passive"))
    )
    (net (code "58") (name "Net-(IC4-SDO)") (class "Default")
      (node (ref "IC4") (pin "7") (pinfunction "SDO_7") (pintype "output"))
      (node (ref "R50") (pin "1") (pinfunction "1_1") (pintype "passive"))
    )
    (net (code "59") (name "Net-(IC4-VINL)") (class "Default")
      (node (ref "IC4") (pin "16") (pinfunction "VINL_16") (pintype "input"))
      (node (ref "IC9") (pin "1") (pinfunction "OUT_1") (pintype "output"))
      (node (ref "R111") (pin "2") (pinfunction "2_2") (pintype "passive"))
      (node (ref "R82") (pin "1") (pinfunction "P$1_1") (pintype "bidirectional"))
    )
    (net (code "60") (name "Net-(IC4-VINR)") (class "Default")
      (node (ref "IC4") (pin "9") (pinfunction "VINR_9") (pintype "input"))
      (node (ref "IC9") (pin "7") (pinfunction "OUT_7") (pintype "output"))
      (node (ref "R83") (pin "1") (pinfunction "P$1_1") (pintype "bidirectional"))
      (node (ref "R93") (pin "2") (pinfunction "2_2") (pintype "passive"))
    )
    (net (code "61") (name "Net-(IC5-SDO)") (class "Default")
      (node (ref "IC5") (pin "7") (pinfunction "SDO_7") (pintype "output"))
      (node (ref "R51") (pin "1") (pinfunction "1_1") (pintype "passive"))
    )
    (net (code "62") (name "Net-(IC5-VINL)") (class "Default")
      (node (ref "IC5") (pin "16") (pinfunction "VINL_16") (pintype "input"))
      (node (ref "R96") (pin "2") (pinfunction "2_2") (pintype "passive"))
      (node (ref "R98") (pin "2") (pinfunction "2_2") (pintype "passive"))
    )
    (net (code "63") (name "Net-(IC5-VINR)") (class "Default")
      (node (ref "IC5") (pin "9") (pinfunction "VINR_9") (pintype "input"))
      (node (ref "R79") (pin "2") (pinfunction "2_2") (pintype "passive"))
      (node (ref "R99") (pin "2") (pinfunction "2_2") (pintype "passive"))
    )
    (net (code "64") (name "Net-(IC6A-+IN)") (class "Default")
      (node (ref "C15") (pin "2") (pinfunction "2_2") (pintype "passive"))
      (node (ref "IC6") (pin "3") (pinfunction "+IN_3") (pintype "input"))
      (node (ref "R15") (pin "2") (pinfunction "2_2") (pintype "passive"))
      (node (ref "R42") (pin "2") (pinfunction "2_2") (pintype "passive"))
    )
    (net (code "65") (name "Net-(IC6A--IN)") (class "Default")
      (node (ref "IC6") (pin "2") (pinfunction "-IN_2") (pintype "input"))
      (node (ref "R64") (pin "2") (pinfunction "P$2_2") (pintype "bidirectional"))
    )
    (net (code "66") (name "Net-(IC6B-+IN)") (class "Default")
      (node (ref "C16") (pin "2") (pinfunction "2_2") (pintype "passive"))
      (node (ref "IC6") (pin "5") (pinfunction "+IN_5") (pintype "input"))
      (node (ref "R16") (pin "2") (pinfunction "2_2") (pintype "passive"))
      (node (ref "R44") (pin "2") (pinfunction "2_2") (pintype "passive"))
    )
    (net (code "67") (name "Net-(IC6B--IN)") (class "Default")
      (node (ref "IC6") (pin "6") (pinfunction "-IN_6") (pintype "input"))
      (node (ref "R65") (pin "2") (pinfunction "P$2_2") (pintype "bidirectional"))
    )
    (net (code "68") (name "Net-(IC7A-+IN)") (class "Default")
      (node (ref "C3") (pin "2") (pinfunction "2_2") (pintype "passive"))
      (node (ref "IC7") (pin "3") (pinfunction "+IN_3") (pintype "input"))
      (node (ref "R2") (pin "2") (pinfunction "2_2") (pintype "passive"))
      (node (ref "R41") (pin "2") (pinfunction "2_2") (pintype "passive"))
    )
    (net (code "69") (name "Net-(IC7A--IN)") (class "Default")
      (node (ref "IC7") (pin "2") (pinfunction "-IN_2") (pintype "input"))
      (node (ref "R114") (pin "2") (pinfunction "P$2_2") (pintype "bidirectional"))
    )
    (net (code "70") (name "Net-(IC7B-+IN)") (class "Default")
      (node (ref "C4") (pin "2") (pinfunction "2_2") (pintype "passive"))
      (node (ref "IC7") (pin "5") (pinfunction "+IN_5") (pintype "input"))
      (node (ref "R4") (pin "2") (pinfunction "2_2") (pintype "passive"))
      (node (ref "R43") (pin "2") (pinfunction "2_2") (pintype "passive"))
    )
    (net (code "71") (name "Net-(IC7B--IN)") (class "Default")
      (node (ref "IC7") (pin "6") (pinfunction "-IN_6") (pintype "input"))
      (node (ref "R66") (pin "2") (pinfunction "P$2_2") (pintype "bidirectional"))
    )
    (net (code "72") (name "Net-(IC8A-+IN)") (class "Default")
      (node (ref "C7") (pin "2") (pinfunction "2_2") (pintype "passive"))
      (node (ref "IC8") (pin "3") (pinfunction "+IN_3") (pintype "input"))
      (node (ref "R58") (pin "2") (pinfunction "2_2") (pintype "passive"))
      (node (ref "R6") (pin "2") (pinfunction "2_2") (pintype "passive"))
    )
    (net (code "73") (name "Net-(IC8A--IN)") (class "Default")
      (node (ref "IC8") (pin "2") (pinfunction "-IN_2") (pintype "input"))
      (node (ref "R80") (pin "2") (pinfunction "P$2_2") (pintype "bidirectional"))
    )
    (net (code "74") (name "Net-(IC8B-+IN)") (class "Default")
      (node (ref "C8") (pin "2") (pinfunction "2_2") (pintype "passive"))
      (node (ref "IC8") (pin "5") (pinfunction "+IN_5") (pintype "input"))
      (node (ref "R59") (pin "2") (pinfunction "2_2") (pintype "passive"))
      (node (ref "R8") (pin "2") (pinfunction "2_2") (pintype "passive"))
    )
    (net (code "75") (name "Net-(IC8B--IN)") (class "Default")
      (node (ref "IC8") (pin "6") (pinfunction "-IN_6") (pintype "input"))
      (node (ref "R81") (pin "2") (pinfunction "P$2_2") (pintype "bidirectional"))
    )
    (net (code "76") (name "Net-(IC9A-+IN)") (class "Default")
      (node (ref "C11") (pin "2") (pinfunction "2_2") (pintype "passive"))
      (node (ref "IC9") (pin "3") (pinfunction "+IN_3") (pintype "input"))
      (node (ref "R10") (pin "2") (pinfunction "2_2") (pintype "passive"))
      (node (ref "R62") (pin "2") (pinfunction "2_2") (pintype "passive"))
    )
    (net (code "77") (name "Net-(IC9A--IN)") (class "Default")
      (node (ref "IC9") (pin "2") (pinfunction "-IN_2") (pintype "input"))
      (node (ref "R82") (pin "2") (pinfunction "P$2_2") (pintype "bidirectional"))
    )
    (net (code "78") (name "Net-(IC9B-+IN)") (class "Default")
      (node (ref "C12") (pin "2") (pinfunction "2_2") (pintype "passive"))
      (node (ref "IC9") (pin "5") (pinfunction "+IN_5") (pintype "input"))
      (node (ref "R12") (pin "2") (pinfunction "2_2") (pintype "passive"))
      (node (ref "R63") (pin "2") (pinfunction "2_2") (pintype "passive"))
    )
    (net (code "79") (name "Net-(IC9B--IN)") (class "Default")
      (node (ref "IC9") (pin "6") (pinfunction "-IN_6") (pintype "input"))
      (node (ref "R83") (pin "2") (pinfunction "P$2_2") (pintype "bidirectional"))
    )
    (net (code "80") (name "Net-(IC10A-+IN)") (class "Default")
      (node (ref "IC10") (pin "3") (pinfunction "+IN_3") (pintype "input"))
      (node (ref "R17") (pin "2") (pinfunction "2_2") (pintype "passive"))
    )
    (net (code "81") (name "Net-(IC10A--IN)") (class "Default")
      (node (ref "IC10") (pin "2") (pinfunction "-IN_2") (pintype "input"))
      (node (ref "R18") (pin "2") (pinfunction "2_2") (pintype "passive"))
      (node (ref "R19") (pin "1") (pinfunction "1_1") (pintype "passive"))
      (node (ref "R20") (pin "1") (pinfunction "1_1") (pintype "passive"))
      (node (ref "R21") (pin "1") (pinfunction "1_1") (pintype "passive"))
    )
    (net (code "82") (name "Net-(IC10A-OUT)") (class "Default")
      (node (ref "IC10") (pin "1") (pinfunction "OUT_1") (pintype "output"))
      (node (ref "R18") (pin "1") (pinfunction "1_1") (pintype "passive"))
      (node (ref "R84") (pin "2") (pinfunction "P$2_2") (pintype "bidirectional"))
    )
    (net (code "83") (name "Net-(IC10B-+IN)") (class "Default")
      (node (ref "IC10") (pin "5") (pinfunction "+IN_5") (pintype "input"))
      (node (ref "R67") (pin "2") (pinfunction "2_2") (pintype "passive"))
    )
    (net (code "84") (name "Net-(IC10B--IN)") (class "Default")
      (node (ref "IC10") (pin "6") (pinfunction "-IN_6") (pintype "input"))
      (node (ref "R68") (pin "2") (pinfunction "2_2") (pintype "passive"))
      (node (ref "R69") (pin "1") (pinfunction "1_1") (pintype "passive"))
    )
    (net (code "85") (name "Net-(IC11A-+IN)") (class "Default")
      (node (ref "IC11") (pin "3") (pinfunction "+IN_3") (pintype "input"))
      (node (ref "R23") (pin "2") (pinfunction "2_2") (pintype "passive"))
    )
    (net (code "86") (name "Net-(IC11A--IN)") (class "Default")
      (node (ref "IC11") (pin "2") (pinfunction "-IN_2") (pintype "input"))
      (node (ref "R24") (pin "1") (pinfunction "1_1") (pintype "passive"))
      (node (ref "R25") (pin "1") (pinfunction "1_1") (pintype "passive"))
      (node (ref "R26") (pin "1") (pinfunction "1_1") (pintype "passive"))
      (node (ref "R28") (pin "2") (pinfunction "2_2") (pintype "passive"))
    )
    (net (code "87") (name "Net-(IC11A-OUT)") (class "Default")
      (node (ref "IC11") (pin "1") (pinfunction "OUT_1") (pintype "output"))
      (node (ref "R28") (pin "1") (pinfunction "1_1") (pintype "passive"))
      (node (ref "R78") (pin "2") (pinfunction "P$2_2") (pintype "bidirectional"))
    )
    (net (code "88") (name "Net-(IC11B-+IN)") (class "Default")
      (node (ref "IC11") (pin "5") (pinfunction "+IN_5") (pintype "input"))
      (node (ref "R70") (pin "2") (pinfunction "2_2") (pintype "passive"))
    )
    (net (code "89") (name "Net-(IC11B--IN)") (class "Default")
      (node (ref "IC11") (pin "6") (pinfunction "-IN_6") (pintype "input"))
      (node (ref "R71") (pin "2") (pinfunction "2_2") (pintype "passive"))
      (node (ref "R72") (pin "1") (pinfunction "1_1") (pintype "passive"))
    )
    (net (code "90") (name "Net-(IC12A-+IN)") (class "Default")
      (node (ref "IC12") (pin "3") (pinfunction "+IN_3") (pintype "input"))
      (node (ref "R29") (pin "2") (pinfunction "2_2") (pintype "passive"))
    )
    (net (code "91") (name "Net-(IC12A--IN)") (class "Default")
      (node (ref "IC12") (pin "2") (pinfunction "-IN_2") (pintype "input"))
      (node (ref "R30") (pin "2") (pinfunction "2_2") (pintype "passive"))
      (node (ref "R32") (pin "1") (pinfunction "1_1") (pintype "passive"))
      (node (ref "R39") (pin "1") (pinfunction "1_1") (pintype "passive"))
    )
    (net (code "92") (name "Net-(IC12A-OUT)") (class "Default")
      (node (ref "IC12") (pin "1") (pinfunction "OUT_1") (pintype "output"))
      (node (ref "R30") (pin "1") (pinfunction "1_1") (pintype "passive"))
      (node (ref "R88") (pin "2") (pinfunction "P$2_2") (pintype "bidirectional"))
    )
    (net (code "93") (name "Net-(IC12B-+IN)") (class "Default")
      (node (ref "IC12") (pin "5") (pinfunction "+IN_5") (pintype "input"))
      (node (ref "R73") (pin "2") (pinfunction "2_2") (pintype "passive"))
    )
    (net (code "94") (name "Net-(IC12B--IN)") (class "Default")
      (node (ref "IC12") (pin "6") (pinfunction "-IN_6") (pintype "input"))
      (node (ref "R74") (pin "2") (pinfunction "2_2") (pintype "passive"))
      (node (ref "R86") (pin "1") (pinfunction "1_1") (pintype "passive"))
    )
    (net (code "95") (name "Net-(IC13A-+IN)") (class "Default")
      (node (ref "IC13") (pin "3") (pinfunction "+IN_3") (pintype "input"))
      (node (ref "R35") (pin "2") (pinfunction "2_2") (pintype "passive"))
    )
    (net (code "96") (name "Net-(IC13A--IN)") (class "Default")
      (node (ref "IC13") (pin "2") (pinfunction "-IN_2") (pintype "input"))
      (node (ref "R36") (pin "1") (pinfunction "1_1") (pintype "passive"))
      (node (ref "R40") (pin "2") (pinfunction "2_2") (pintype "passive"))
      (node (ref "R45") (pin "1") (pinfunction "1_1") (pintype "passive"))
    )
    (net (code "97") (name "Net-(IC13A-OUT)") (class "Default")
      (node (ref "IC13") (pin "1") (pinfunction "OUT_1") (pintype "output"))
      (node (ref "R40") (pin "1") (pinfunction "1_1") (pintype "passive"))
      (node (ref "R91") (pin "2") (pinfunction "P$2_2") (pintype "bidirectional"))
    )
    (net (code "98") (name "Net-(IC13B-+IN)") (class "Default")
      (node (ref "IC13") (pin "5") (pinfunction "+IN_5") (pintype "input"))
      (node (ref "R76") (pin "2") (pinfunction "2_2") (pintype "passive"))
    )
    (net (code "99") (name "Net-(IC13B--IN)") (class "Default")
      (node (ref "IC13") (pin "6") (pinfunction "-IN_6") (pintype "input"))
      (node (ref "R77") (pin "2") (pinfunction "2_2") (pintype "passive"))
      (node (ref "R89") (pin "1") (pinfunction "1_1") (pintype "passive"))
    )
    (net (code "100") (name "Net-(IC14-SDO)") (class "Default")
      (node (ref "IC14") (pin "7") (pinfunction "SDO_7") (pintype "output"))
      (node (ref "R92") (pin "1") (pinfunction "1_1") (pintype "passive"))
    )
    (net (code "101") (name "Net-(IC14-VINL)") (class "Default")
      (node (ref "C65") (pin "2") (pinfunction "2_2") (pintype "passive"))
      (node (ref "IC14") (pin "16") (pinfunction "VINL_16") (pintype "input"))
      (node (ref "R101") (pin "2") (pinfunction "2_2") (pintype "passive"))
      (node (ref "R107") (pin "2") (pinfunction "2_2") (pintype "passive"))
    )
    (net (code "102") (name "Net-(IC14-VINR)") (class "Default")
      (node (ref "C66") (pin "2") (pinfunction "2_2") (pintype "passive"))
      (node (ref "IC14") (pin "9") (pinfunction "VINR_9") (pintype "input"))
      (node (ref "R102") (pin "2") (pinfunction "2_2") (pintype "passive"))
      (node (ref "R108") (pin "2") (pinfunction "2_2") (pintype "passive"))
    )
    (net (code "103") (name "Net-(JP1-Pad2)") (class "Default")
      (node (ref "JP1") (pin "2") (pinfunction "2_2") (pintype "passive"))
      (node (ref "R96") (pin "1") (pinfunction "1_1") (pintype "passive"))
    )
    (net (code "104") (name "Net-(JP2-Pad2)") (class "Default")
      (node (ref "JP2") (pin "2") (pinfunction "2_2") (pintype "passive"))
      (node (ref "R79") (pin "1") (pinfunction "1_1") (pintype "passive"))
    )
    (net (code "105") (name "Net-(JP3-Pad1)") (class "Default")
      (node (ref "JP3") (pin "1") (pinfunction "1_1") (pintype "passive"))
      (node (ref "R115") (pin "1") (pinfunction "1_1") (pintype "passive"))
      (node (ref "R97") (pin "1") (pinfunction "1_1") (pintype "passive"))
    )
    (net (code "106") (name "Net-(LED2-PadA)") (class "Default")
      (node (ref "LED2") (pin "A") (pinfunction "A_A") (pintype "passive"))
      (node (ref "U$11") (pin "1") (pinfunction "1_1") (pintype "bidirectional"))
    )
    (net (code "107") (name "Net-(LED2-PadC)") (class "Default")
      (node (ref "LED2") (pin "C") (pinfunction "C_C") (pintype "passive"))
      (node (ref "R33") (pin "2") (pinfunction "2_2") (pintype "passive"))
    )
    (net (code "108") (name "Net-(Q1-G)") (class "Default")
      (node (ref "C57") (pin "1") (pinfunction "1_1") (pintype "passive"))
      (node (ref "Q1") (pin "1") (pinfunction "G_1") (pintype "passive"))
      (node (ref "R37") (pin "1") (pinfunction "1_1") (pintype "passive"))
      (node (ref "T1") (pin "3") (pinfunction "C_3") (pintype "passive"))
    )
    (net (code "109") (name "Net-(R22-Pad2)") (class "Default")
      (node (ref "R22") (pin "2") (pinfunction "2_2") (pintype "passive"))
      (node (ref "U$11") (pin "34") (pinfunction "34_34") (pintype "bidirectional"))
    )
    (net (code "110") (name "Net-(R27-Pad2)") (class "Default")
      (node (ref "R27") (pin "2") (pinfunction "2_2") (pintype "passive"))
      (node (ref "U$11") (pin "33") (pinfunction "33_33") (pintype "bidirectional"))
    )
    (net (code "111") (name "Net-(R78-P$1)") (class "Default")
      (node (ref "R72") (pin "2") (pinfunction "2_2") (pintype "passive"))
      (node (ref "R75") (pin "1") (pinfunction "1_1") (pintype "passive"))
      (node (ref "R78") (pin "1") (pinfunction "P$1_1") (pintype "bidirectional"))
    )
    (net (code "112") (name "Net-(R84-P$1)") (class "Default")
      (node (ref "R69") (pin "2") (pinfunction "2_2") (pintype "passive"))
      (node (ref "R84") (pin "1") (pinfunction "P$1_1") (pintype "bidirectional"))
      (node (ref "R85") (pin "1") (pinfunction "1_1") (pintype "passive"))
    )
    (net (code "113") (name "Net-(R88-P$1)") (class "Default")
      (node (ref "R86") (pin "2") (pinfunction "2_2") (pintype "passive"))
      (node (ref "R87") (pin "1") (pinfunction "1_1") (pintype "passive"))
      (node (ref "R88") (pin "1") (pinfunction "P$1_1") (pintype "bidirectional"))
    )
    (net (code "114") (name "Net-(R91-P$1)") (class "Default")
      (node (ref "R89") (pin "2") (pinfunction "2_2") (pintype "passive"))
      (node (ref "R90") (pin "1") (pinfunction "1_1") (pintype "passive"))
      (node (ref "R91") (pin "1") (pinfunction "P$1_1") (pintype "bidirectional"))
    )
    (net (code "115") (name "Net-(T1-B)") (class "Default")
      (node (ref "R38") (pin "2") (pinfunction "2_2") (pintype "passive"))
      (node (ref "R46") (pin "1") (pinfunction "1_1") (pintype "passive"))
      (node (ref "T1") (pin "1") (pinfunction "B_1") (pintype "passive"))
    )
    (net (code "116") (name "Net-(U1-BP)") (class "Default")
      (node (ref "C73") (pin "2") (pinfunction "2_2") (pintype "passive"))
      (node (ref "U1") (pin "4") (pinfunction "BP_4") (pintype "input"))
    )
    (net (code "117") (name "Net-(X5A-KL)") (class "Default")
      (node (ref "U$2") (pin "P$1") (pinfunction "P$1_P$1") (pintype "bidirectional"))
      (node (ref "X5") (pin "1") (pinfunction "KL_1") (pintype "passive"))
    )
    (net (code "118") (name "Net-(X5C-KL)") (class "Default")
      (node (ref "U$13") (pin "P$1") (pinfunction "P$1_P$1") (pintype "bidirectional"))
      (node (ref "X5") (pin "11") (pinfunction "KL_11") (pintype "passive"))
    )
    (net (code "119") (name "Net-(X5F-KL)") (class "Default")
      (node (ref "U$5") (pin "P$1") (pinfunction "P$1_P$1") (pintype "bidirectional"))
      (node (ref "X5") (pin "3") (pinfunction "KL_3") (pintype "passive"))
    )
    (net (code "120") (name "Net-(X5H-KL)") (class "Default")
      (node (ref "U$6") (pin "P$1") (pinfunction "P$1_P$1") (pintype "bidirectional"))
      (node (ref "X5") (pin "5") (pinfunction "KL_5") (pintype "passive"))
    )
    (net (code "121") (name "Net-(X5J-KL)") (class "Default")
      (node (ref "U$9") (pin "P$1") (pinfunction "P$1_P$1") (pintype "bidirectional"))
      (node (ref "X5") (pin "7") (pinfunction "KL_7") (pintype "passive"))
    )
    (net (code "122") (name "Net-(X5L-KL)") (class "Default")
      (node (ref "U$12") (pin "P$1") (pinfunction "P$1_P$1") (pintype "bidirectional"))
      (node (ref "X5") (pin "9") (pinfunction "KL_9") (pintype "passive"))
    )
    (net (code "123") (name "Net-(Y1-1)") (class "Default")
      (node (ref "C56") (pin "1") (pinfunction "1_1") (pintype "passive"))
      (node (ref "U$11") (pin "9") (pinfunction "9_9") (pintype "bidirectional"))
      (node (ref "Y1") (pin "P$1") (pinfunction "1_P$1") (pintype "passive"))
    )
    (net (code "124") (name "Net-(Y1-2)") (class "Default")
      (node (ref "C55") (pin "1") (pinfunction "1_1") (pintype "passive"))
      (node (ref "U$11") (pin "8") (pinfunction "8_8") (pintype "bidirectional"))
      (node (ref "Y1") (pin "P$2") (pinfunction "2_P$2") (pintype "passive"))
    )
    (net (code "125") (name "PGA_EN") (class "Default")
      (node (ref "R46") (pin "2") (pinfunction "2_2") (pintype "passive"))
      (node (ref "U$11") (pin "14") (pinfunction "14_14") (pintype "bidirectional"))
    )
    (net (code "126") (name "REAR_L") (class "Default")
      (node (ref "C5") (pin "1") (pinfunction "1_1") (pintype "passive"))
      (node (ref "R52") (pin "2") (pinfunction "2_2") (pintype "passive"))
      (node (ref "X4") (pin "11") (pinfunction "KL_11") (pintype "passive"))
    )
    (net (code "127") (name "REAR_R") (class "Default")
      (node (ref "C6") (pin "1") (pinfunction "1_1") (pintype "passive"))
      (node (ref "R53") (pin "2") (pinfunction "2_2") (pintype "passive"))
      (node (ref "X4") (pin "12") (pinfunction "KL_12") (pintype "passive"))
    )
    (net (code "128") (name "RST") (class "Default")
      (node (ref "R34") (pin "1") (pinfunction "1_1") (pintype "passive"))
      (node (ref "U$11") (pin "48") (pinfunction "48_48") (pintype "bidirectional"))
      (node (ref "X1") (pin "2") (pinfunction "2_2") (pintype "passive"))
    )
    (net (code "129") (name "RX{slash}SDA") (class "Default")
      (node (ref "R22") (pin "1") (pinfunction "1_1") (pintype "passive"))
      (node (ref "R97") (pin "2") (pinfunction "2_2") (pintype "passive"))
      (node (ref "X1") (pin "5") (pinfunction "5_5") (pintype "passive"))
      (node (ref "X3") (pin "2") (pinfunction "2_2") (pintype "passive"))
    )
    (net (code "130") (name "SPDIF_L") (class "Default")
      (node (ref "C13") (pin "1") (pinfunction "1_1") (pintype "passive"))
      (node (ref "R56") (pin "2") (pinfunction "2_2") (pintype "passive"))
      (node (ref "X4") (pin "8") (pinfunction "KL_8") (pintype "passive"))
    )
    (net (code "131") (name "SPDIF_R") (class "Default")
      (node (ref "C14") (pin "1") (pinfunction "1_1") (pintype "passive"))
      (node (ref "R57") (pin "2") (pinfunction "2_2") (pintype "passive"))
      (node (ref "X4") (pin "9") (pinfunction "KL_9") (pintype "passive"))
    )
    (net (code "132") (name "SW") (class "Default")
      (node (ref "C68") (pin "1") (pinfunction "1_1") (pintype "passive"))
      (node (ref "R104") (pin "2") (pinfunction "2_2") (pintype "passive"))
      (node (ref "X4") (pin "16") (pinfunction "KL_16") (pintype "passive"))
    )
    (net (code "133") (name "TEST") (class "Default")
      (node (ref "R31") (pin "1") (pinfunction "1_1") (pintype "passive"))
      (node (ref "U$11") (pin "47") (pinfunction "47_47") (pintype "input"))
      (node (ref "X1") (pin "3") (pinfunction "3_3") (pintype "passive"))
    )
    (net (code "134") (name "TX{slash}SCL") (class "Default")
      (node (ref "R115") (pin "2") (pinfunction "2_2") (pintype "passive"))
      (node (ref "R27") (pin "1") (pinfunction "1_1") (pintype "passive"))
      (node (ref "X1") (pin "6") (pinfunction "6_6") (pintype "passive"))
      (node (ref "X3") (pin "3") (pinfunction "3_3") (pintype "passive"))
    )
    (net (code "135") (name "V_FRONT1") (class "Default")
      (node (ref "IC5") (pin "14") (pinfunction "VOUTL_14") (pintype "output"))
      (node (ref "R32") (pin "2") (pinfunction "2_2") (pintype "passive"))
    )
    (net (code "136") (name "V_FRONT2") (class "Default")
      (node (ref "IC5") (pin "11") (pinfunction "VOUTR_11") (pintype "output"))
      (node (ref "R36") (pin "2") (pinfunction "2_2") (pintype "passive"))
    )
    (net (code "137") (name "V_FRONT_L") (class "Default")
      (node (ref "IC1") (pin "14") (pinfunction "VOUTL_14") (pintype "output"))
      (node (ref "R19") (pin "2") (pinfunction "2_2") (pintype "passive"))
    )
    (net (code "138") (name "V_FRONT_R") (class "Default")
      (node (ref "IC1") (pin "11") (pinfunction "VOUTR_11") (pintype "output"))
      (node (ref "R24") (pin "2") (pinfunction "2_2") (pintype "passive"))
    )
    (net (code "139") (name "V_LINE_L") (class "Default")
      (node (ref "IC3") (pin "14") (pinfunction "VOUTL_14") (pintype "output"))
      (node (ref "R20") (pin "2") (pinfunction "2_2") (pintype "passive"))
    )
    (net (code "140") (name "V_LINE_R") (class "Default")
      (node (ref "IC3") (pin "11") (pinfunction "VOUTR_11") (pintype "output"))
      (node (ref "R25") (pin "2") (pinfunction "2_2") (pintype "passive"))
    )
    (net (code "141") (name "V_REAR_L") (class "Default")
      (node (ref "IC2") (pin "14") (pinfunction "VOUTL_14") (pintype "output"))
      (node (ref "R39") (pin "2") (pinfunction "2_2") (pintype "passive"))
    )
    (net (code "142") (name "V_REAR_R") (class "Default")
      (node (ref "IC2") (pin "11") (pinfunction "VOUTR_11") (pintype "output"))
      (node (ref "R45") (pin "2") (pinfunction "2_2") (pintype "passive"))
    )
    (net (code "143") (name "V_SPDIF_L") (class "Default")
      (node (ref "IC4") (pin "14") (pinfunction "VOUTL_14") (pintype "output"))
      (node (ref "R21") (pin "2") (pinfunction "2_2") (pintype "passive"))
    )
    (net (code "144") (name "V_SPDIF_R") (class "Default")
      (node (ref "IC4") (pin "11") (pinfunction "VOUTR_11") (pintype "output"))
      (node (ref "R26") (pin "2") (pinfunction "2_2") (pintype "passive"))
    )
    (net (code "145") (name "unconnected-(U$11-Pad2)") (class "Default")
      (node (ref "U$11") (pin "2") (pinfunction "2_2") (pintype "bidirectional"))
    )
    (net (code "146") (name "unconnected-(U$11-Pad3)") (class "Default")
      (node (ref "U$11") (pin "3") (pinfunction "3_3") (pintype "bidirectional"))
    )
    (net (code "147") (name "unconnected-(U$11-Pad4)") (class "Default")
      (node (ref "U$11") (pin "4") (pinfunction "4_4") (pintype "bidirectional"))
    )
    (net (code "148") (name "unconnected-(U$11-Pad5)") (class "Default")
      (node (ref "U$11") (pin "5") (pinfunction "5_5") (pintype "bidirectional"))
    )
    (net (code "149") (name "unconnected-(U$11-Pad6)") (class "Default")
      (node (ref "U$11") (pin "6") (pinfunction "6_6") (pintype "bidirectional"))
    )
    (net (code "150") (name "unconnected-(U$11-Pad23)") (class "Default")
      (node (ref "U$11") (pin "23") (pinfunction "23_23") (pintype "bidirectional"))
    )
    (net (code "151") (name "unconnected-(U$11-Pad24)") (class "Default")
      (node (ref "U$11") (pin "24") (pinfunction "24_24") (pintype "bidirectional"))
    )
    (net (code "152") (name "unconnected-(U$11-Pad25)") (class "Default")
      (node (ref "U$11") (pin "25") (pinfunction "25_25") (pintype "bidirectional"))
    )
    (net (code "153") (name "unconnected-(U$11-Pad26)") (class "Default")
      (node (ref "U$11") (pin "26") (pinfunction "26_26") (pintype "bidirectional"))
    )
    (net (code "154") (name "unconnected-(U$11-Pad38)") (class "Default")
      (node (ref "U$11") (pin "38") (pinfunction "38_38") (pintype "bidirectional"))
    )
    (net (code "155") (name "unconnected-(U$11-Pad40)") (class "Default")
      (node (ref "U$11") (pin "40") (pinfunction "40_40") (pintype "bidirectional"))
    )
    (net (code "156") (name "unconnected-(U$11-Pad45)") (class "Default")
      (node (ref "U$11") (pin "45") (pinfunction "45_45") (pintype "bidirectional"))
    )
  )
)
